# bristol_longshot.net
KiCad netlist of a schematic drawn in EAGLE
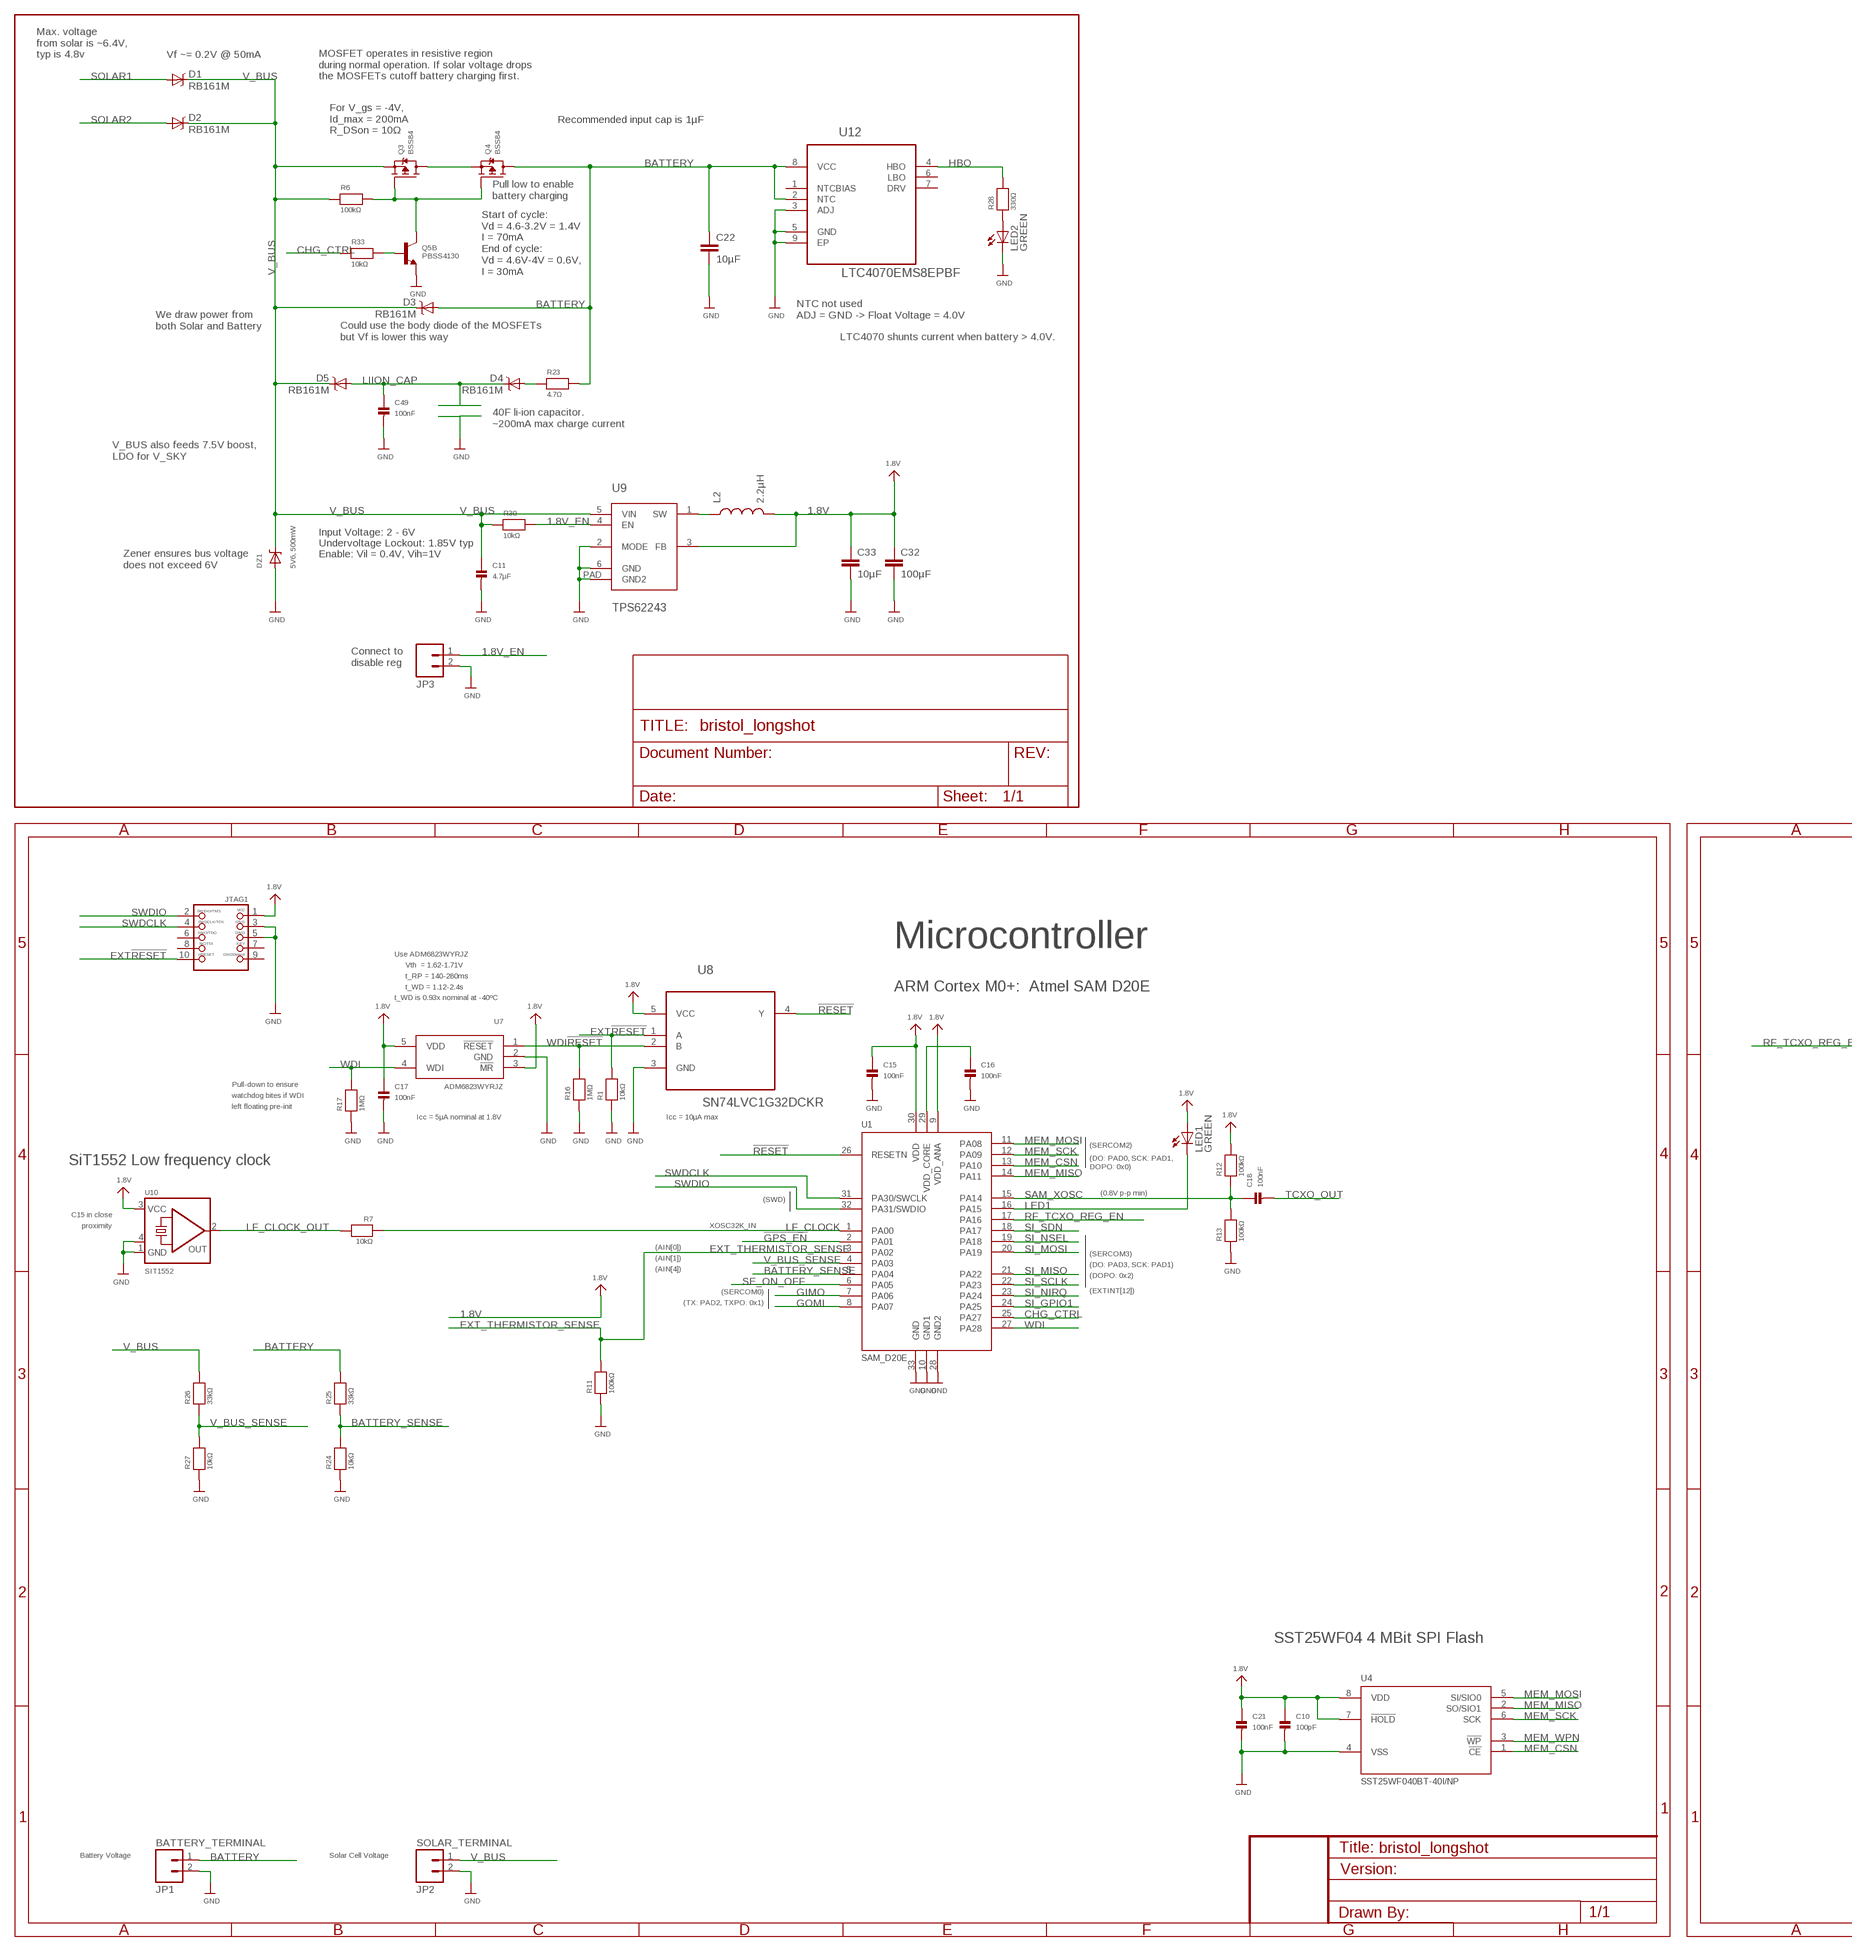
[diagram p0: schematic, sheet 1, part 1 of 3]
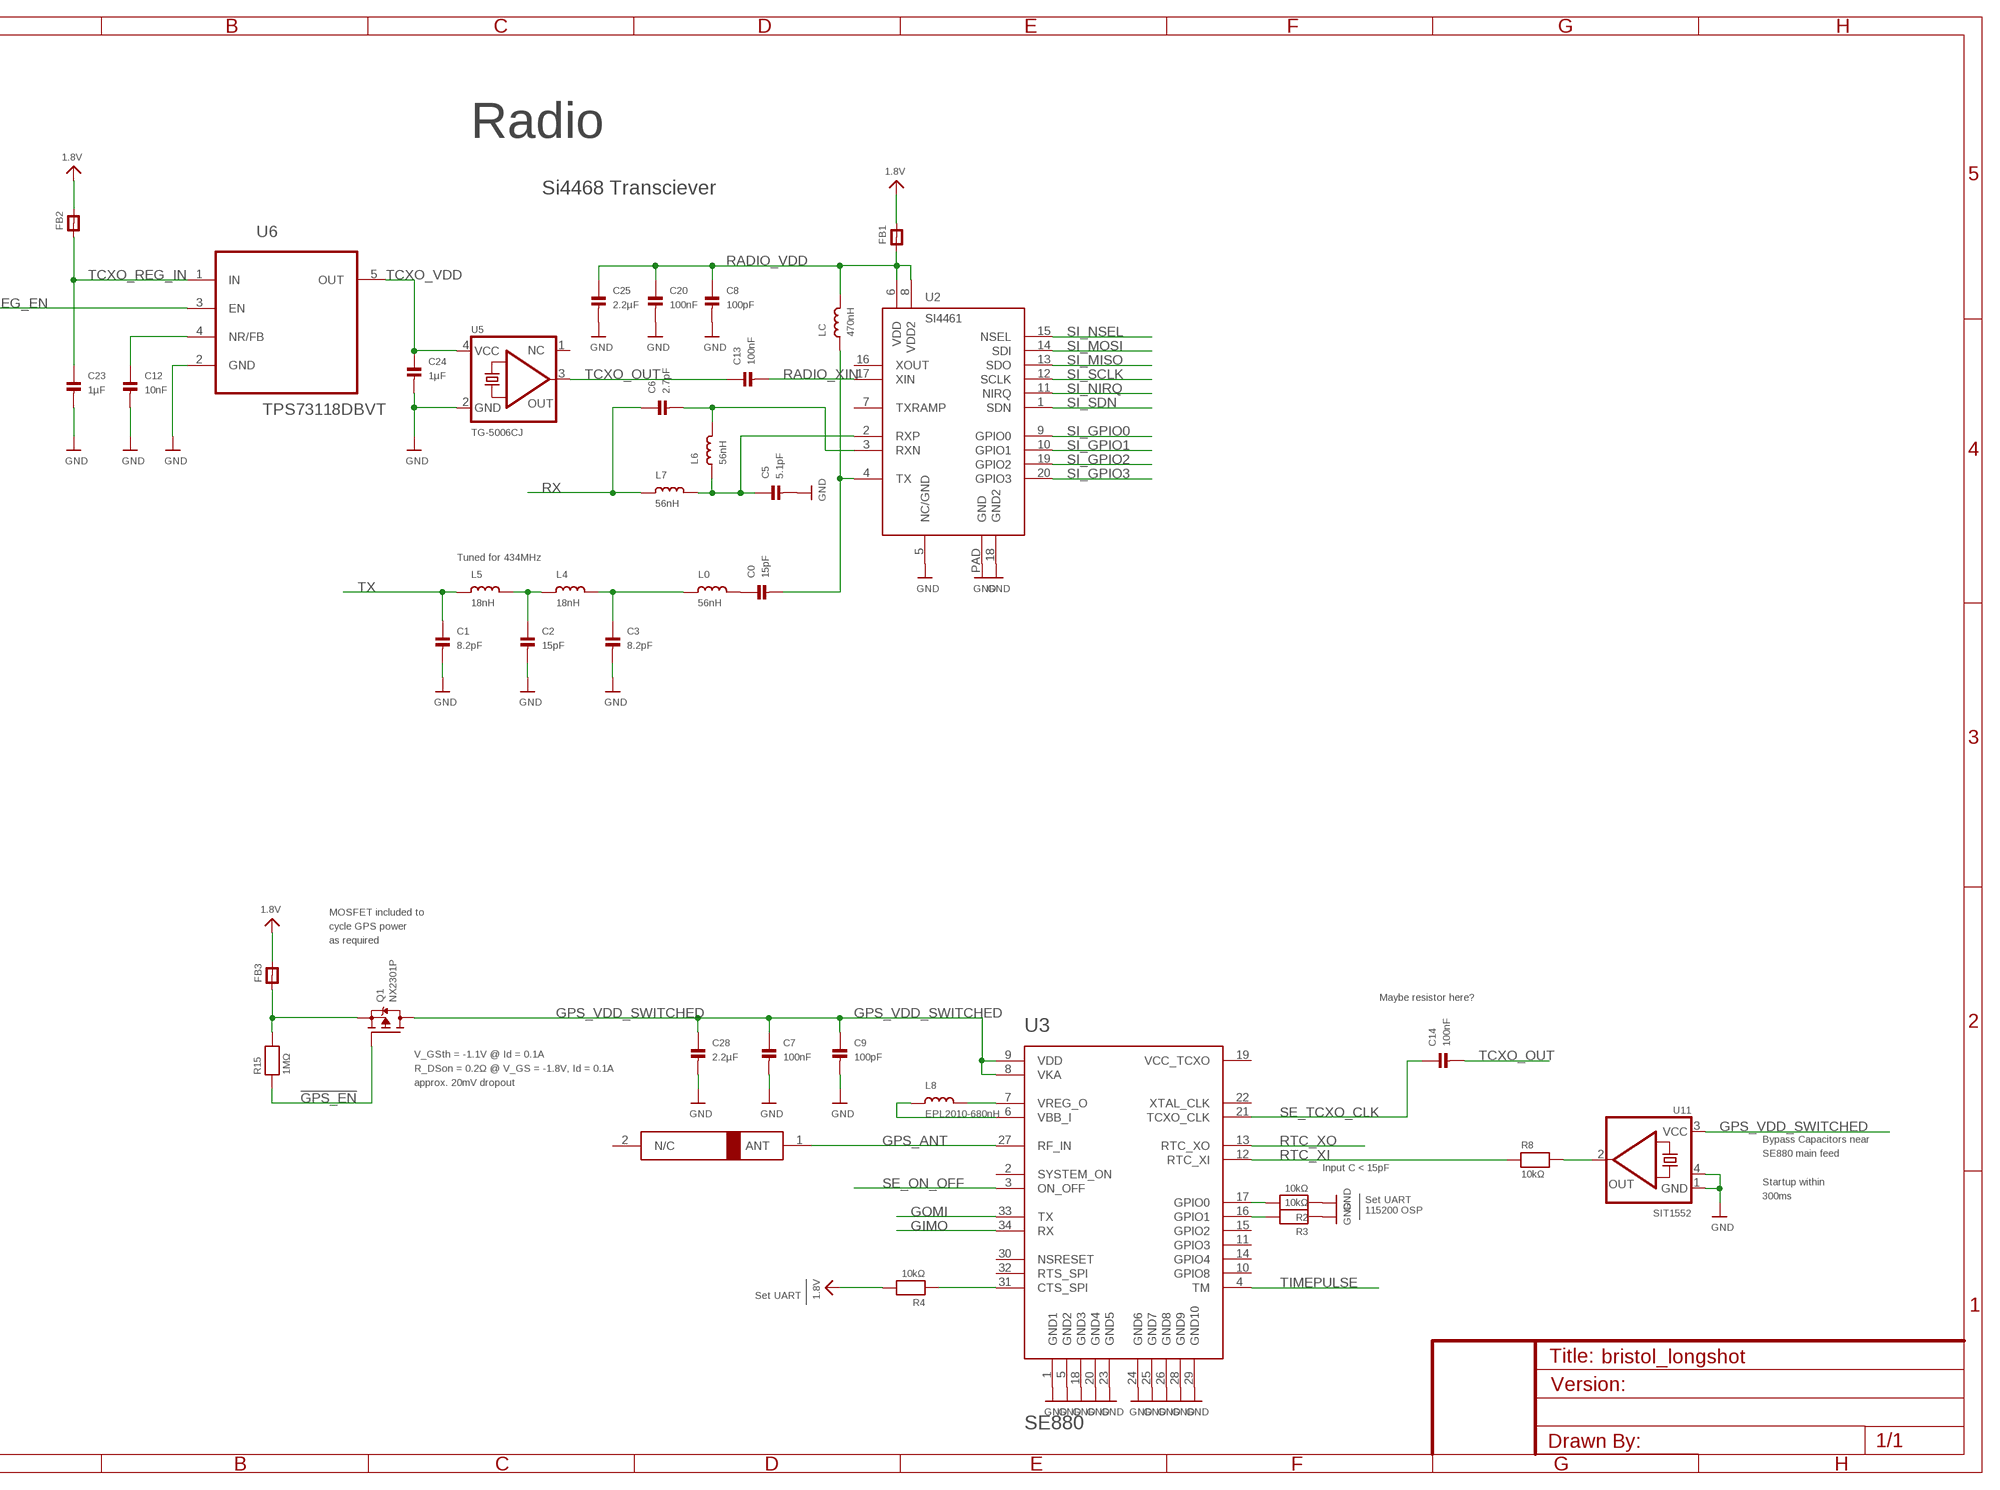
[diagram p1: schematic, sheet 1, part 2 of 3]
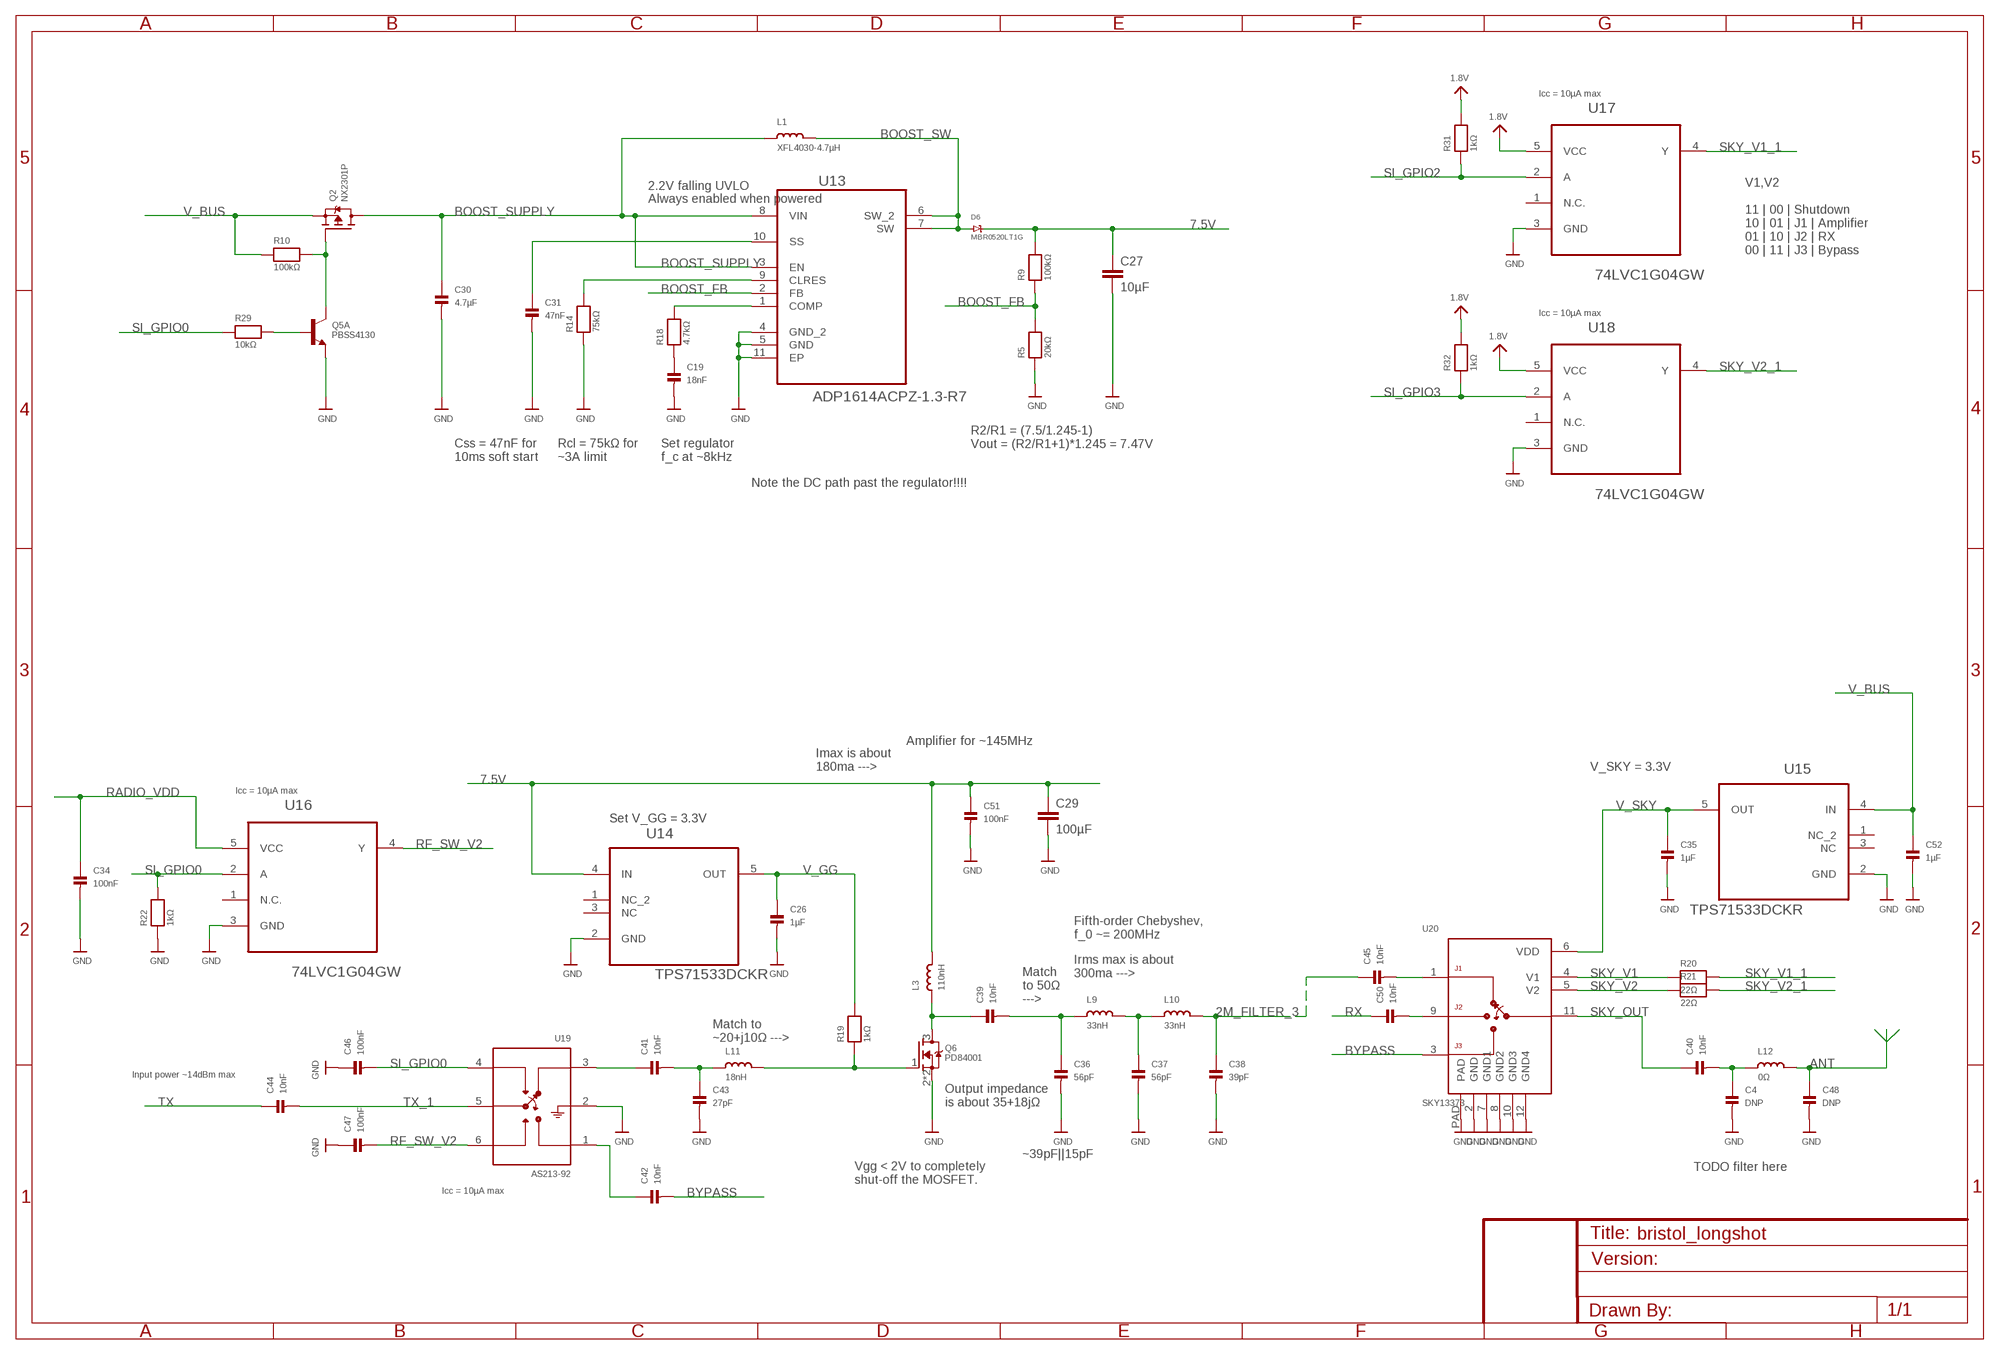
[diagram p2: schematic, sheet 1, part 3 of 3]

(export (version "E")
  (design (tool "Eeschema 10.0.6"))
  (components
    (comp (ref "A1")
      (value "1575AT43A40")
      (footprint "eagle-import:1575AT43A40")
      (libsource (lib "eagle-import") (part "1575AT43A40"))
    )
    (comp (ref "C0")
      (value "15pF")
      (footprint "eagle-import:_0402")
      (libsource (lib "eagle-import") (part "CAP_CERAMIC_0402"))
    )
    (comp (ref "C1")
      (value "8.2pF")
      (footprint "eagle-import:_0402")
      (libsource (lib "eagle-import") (part "CAP_CERAMIC_0402"))
    )
    (comp (ref "C2")
      (value "15pF")
      (footprint "eagle-import:_0402")
      (libsource (lib "eagle-import") (part "CAP_CERAMIC_0402"))
    )
    (comp (ref "C3")
      (value "8.2pF")
      (footprint "eagle-import:_0402")
      (libsource (lib "eagle-import") (part "CAP_CERAMIC_0402"))
    )
    (comp (ref "C4")
      (value "DNP")
      (footprint "eagle-import:_0402")
      (libsource (lib "eagle-import") (part "CAP_CERAMIC_0402"))
    )
    (comp (ref "C5")
      (value "5.1pF")
      (footprint "eagle-import:_0402")
      (libsource (lib "eagle-import") (part "CAP_CERAMIC_0402"))
    )
    (comp (ref "C6")
      (value "2.7pF")
      (footprint "eagle-import:_0402")
      (libsource (lib "eagle-import") (part "CAP_CERAMIC_0402"))
    )
    (comp (ref "C7")
      (value "100nF")
      (footprint "eagle-import:_0402")
      (libsource (lib "eagle-import") (part "CAP_CERAMIC_0402"))
    )
    (comp (ref "C8")
      (value "100pF")
      (footprint "eagle-import:_0402")
      (libsource (lib "eagle-import") (part "CAP_CERAMIC_0402"))
    )
    (comp (ref "C9")
      (value "100pF")
      (footprint "eagle-import:_0402")
      (libsource (lib "eagle-import") (part "CAP_CERAMIC_0402"))
    )
    (comp (ref "C10")
      (value "100pF")
      (footprint "eagle-import:_0402")
      (libsource (lib "eagle-import") (part "CAP_CERAMIC_0402"))
    )
    (comp (ref "C11")
      (value "4.7µF")
      (footprint "eagle-import:_0402")
      (libsource (lib "eagle-import") (part "CAP_CERAMIC_0402"))
    )
    (comp (ref "C12")
      (value "10nF")
      (footprint "eagle-import:_0402")
      (libsource (lib "eagle-import") (part "CAP_CERAMIC_0402"))
    )
    (comp (ref "C13")
      (value "100nF")
      (footprint "eagle-import:_0402")
      (libsource (lib "eagle-import") (part "CAP_CERAMIC_0402"))
    )
    (comp (ref "C14")
      (value "100nF")
      (footprint "eagle-import:_0402")
      (libsource (lib "eagle-import") (part "CAP_CERAMIC_0402"))
    )
    (comp (ref "C15")
      (value "100nF")
      (footprint "eagle-import:_0402")
      (libsource (lib "eagle-import") (part "CAP_CERAMIC_0402"))
    )
    (comp (ref "C16")
      (value "100nF")
      (footprint "eagle-import:_0402")
      (libsource (lib "eagle-import") (part "CAP_CERAMIC_0402"))
    )
    (comp (ref "C17")
      (value "100nF")
      (footprint "eagle-import:_0402")
      (libsource (lib "eagle-import") (part "CAP_CERAMIC_0402"))
    )
    (comp (ref "C18")
      (value "100nF")
      (footprint "eagle-import:_0402")
      (libsource (lib "eagle-import") (part "CAP_CERAMIC_0402"))
    )
    (comp (ref "C19")
      (value "18nF")
      (footprint "eagle-import:_0402")
      (libsource (lib "eagle-import") (part "CAP_CERAMIC_0402"))
    )
    (comp (ref "C20")
      (value "100nF")
      (footprint "eagle-import:_0402")
      (libsource (lib "eagle-import") (part "CAP_CERAMIC_0402"))
    )
    (comp (ref "C21")
      (value "100nF")
      (footprint "eagle-import:_0402")
      (libsource (lib "eagle-import") (part "CAP_CERAMIC_0402"))
    )
    (comp (ref "C22")
      (value "10µF")
      (footprint "eagle-import:C0603K")
      (libsource (lib "eagle-import") (part "C-EUC0603K"))
    )
    (comp (ref "C23")
      (value "1µF")
      (footprint "eagle-import:_0402")
      (libsource (lib "eagle-import") (part "CAP_CERAMIC_0402"))
    )
    (comp (ref "C24")
      (value "1µF")
      (footprint "eagle-import:_0402")
      (libsource (lib "eagle-import") (part "CAP_CERAMIC_0402"))
    )
    (comp (ref "C25")
      (value "2.2µF")
      (footprint "eagle-import:_0402")
      (libsource (lib "eagle-import") (part "CAP_CERAMIC_0402"))
    )
    (comp (ref "C26")
      (value "1µF")
      (footprint "eagle-import:_0402")
      (libsource (lib "eagle-import") (part "CAP_CERAMIC_0402"))
    )
    (comp (ref "C27")
      (value "10µF")
      (footprint "eagle-import:C0603K")
      (libsource (lib "eagle-import") (part "C-EUC0603K"))
    )
    (comp (ref "C28")
      (value "2.2µF")
      (footprint "eagle-import:_0402")
      (libsource (lib "eagle-import") (part "CAP_CERAMIC_0402"))
    )
    (comp (ref "C29")
      (value "100µF")
      (footprint "eagle-import:C1206K")
      (libsource (lib "eagle-import") (part "C-EUC1206K"))
    )
    (comp (ref "C30")
      (value "4.7µF")
      (footprint "eagle-import:_0402")
      (libsource (lib "eagle-import") (part "CAP_CERAMIC_0402"))
    )
    (comp (ref "C31")
      (value "47nF")
      (footprint "eagle-import:_0402")
      (libsource (lib "eagle-import") (part "CAP_CERAMIC_0402"))
    )
    (comp (ref "C32")
      (value "100µF")
      (footprint "eagle-import:C1206K")
      (libsource (lib "eagle-import") (part "C-EUC1206K"))
    )
    (comp (ref "C33")
      (value "10µF")
      (footprint "eagle-import:C0603K")
      (libsource (lib "eagle-import") (part "C-EUC0603K"))
    )
    (comp (ref "C34")
      (value "100nF")
      (footprint "eagle-import:_0402")
      (libsource (lib "eagle-import") (part "CAP_CERAMIC_0402"))
    )
    (comp (ref "C35")
      (value "1µF")
      (footprint "eagle-import:_0402")
      (libsource (lib "eagle-import") (part "CAP_CERAMIC_0402"))
    )
    (comp (ref "C36")
      (value "56pF")
      (footprint "eagle-import:_0402")
      (libsource (lib "eagle-import") (part "CAP_CERAMIC_0402"))
    )
    (comp (ref "C37")
      (value "56pF")
      (footprint "eagle-import:_0402")
      (libsource (lib "eagle-import") (part "CAP_CERAMIC_0402"))
    )
    (comp (ref "C38")
      (value "39pF")
      (footprint "eagle-import:_0402")
      (libsource (lib "eagle-import") (part "CAP_CERAMIC_0402"))
    )
    (comp (ref "C39")
      (value "10nF")
      (footprint "eagle-import:_0402")
      (libsource (lib "eagle-import") (part "CAP_CERAMIC_0402"))
    )
    (comp (ref "C40")
      (value "10nF")
      (footprint "eagle-import:_0402")
      (libsource (lib "eagle-import") (part "CAP_CERAMIC_0402"))
    )
    (comp (ref "C41")
      (value "10nF")
      (footprint "eagle-import:_0402")
      (libsource (lib "eagle-import") (part "CAP_CERAMIC_0402"))
    )
    (comp (ref "C42")
      (value "10nF")
      (footprint "eagle-import:_0402")
      (libsource (lib "eagle-import") (part "CAP_CERAMIC_0402"))
    )
    (comp (ref "C43")
      (value "27pF")
      (footprint "eagle-import:_0402")
      (libsource (lib "eagle-import") (part "CAP_CERAMIC_0402"))
    )
    (comp (ref "C44")
      (value "10nF")
      (footprint "eagle-import:_0402")
      (libsource (lib "eagle-import") (part "CAP_CERAMIC_0402"))
    )
    (comp (ref "C45")
      (value "10nF")
      (footprint "eagle-import:_0402")
      (libsource (lib "eagle-import") (part "CAP_CERAMIC_0402"))
    )
    (comp (ref "C46")
      (value "100nF")
      (footprint "eagle-import:_0402")
      (libsource (lib "eagle-import") (part "CAP_CERAMIC_0402"))
    )
    (comp (ref "C47")
      (value "100nF")
      (footprint "eagle-import:_0402")
      (libsource (lib "eagle-import") (part "CAP_CERAMIC_0402"))
    )
    (comp (ref "C48")
      (value "DNP")
      (footprint "eagle-import:_0402")
      (libsource (lib "eagle-import") (part "CAP_CERAMIC_0402"))
    )
    (comp (ref "C49")
      (value "100nF")
      (footprint "eagle-import:_0402")
      (libsource (lib "eagle-import") (part "CAP_CERAMIC_0402"))
    )
    (comp (ref "C50")
      (value "10nF")
      (footprint "eagle-import:_0805")
      (libsource (lib "eagle-import") (part "CAP_CERAMIC_0805"))
    )
    (comp (ref "C51")
      (value "100nF")
      (footprint "eagle-import:_0402")
      (libsource (lib "eagle-import") (part "CAP_CERAMIC_0402"))
    )
    (comp (ref "C52")
      (value "1µF")
      (footprint "eagle-import:_0402")
      (libsource (lib "eagle-import") (part "CAP_CERAMIC_0402"))
    )
    (comp (ref "D1")
      (value "RB161M")
      (footprint "eagle-import:RB161M")
      (libsource (lib "eagle-import") (part "RB161M"))
    )
    (comp (ref "D2")
      (value "RB161M")
      (footprint "eagle-import:RB161M")
      (libsource (lib "eagle-import") (part "RB161M"))
    )
    (comp (ref "D3")
      (value "RB161M")
      (footprint "eagle-import:RB161M")
      (libsource (lib "eagle-import") (part "RB161M"))
    )
    (comp (ref "D4")
      (value "RB161M")
      (footprint "eagle-import:RB161M")
      (libsource (lib "eagle-import") (part "RB161M"))
    )
    (comp (ref "D5")
      (value "RB161M")
      (footprint "eagle-import:RB161M")
      (libsource (lib "eagle-import") (part "RB161M"))
    )
    (comp (ref "D6")
      (value "MBR0520LT1G")
      (footprint "eagle-import:SOD123W")
      (libsource (lib "eagle-import") (part "DIODE[SCHOTKY]-SOD123W"))
    )
    (comp (ref "DZ1")
      (value "5V6, 500mW")
      (footprint "eagle-import:SOD-323")
      (libsource (lib "eagle-import") (part "DIODE-ZENERSOD"))
    )
    (comp (ref "FB1")
      (value "FERRITE_0402")
      (footprint "eagle-import:_0402")
      (libsource (lib "eagle-import") (part "FERRITE_0402"))
    )
    (comp (ref "FB2")
      (value "FERRITE_0402")
      (footprint "eagle-import:_0402")
      (libsource (lib "eagle-import") (part "FERRITE_0402"))
    )
    (comp (ref "FB3")
      (value "FERRITE_0603")
      (footprint "eagle-import:_0603")
      (libsource (lib "eagle-import") (part "FERRITE_0603"))
    )
    (comp (ref "JP1")
      (value "BATTERY_TERMINAL")
      (footprint "eagle-import:1X02_LOCK")
      (libsource (lib "eagle-import") (part "M02LOCK"))
    )
    (comp (ref "JP2")
      (value "SOLAR_TERMINAL")
      (footprint "eagle-import:1X02_LOCK")
      (libsource (lib "eagle-import") (part "M02LOCK"))
    )
    (comp (ref "JP3")
      (value "M02LOCK")
      (footprint "eagle-import:1X02_LOCK")
      (libsource (lib "eagle-import") (part "M02LOCK"))
    )
    (comp (ref "JTAG1")
      (value "JTAG-CORTEXM3SMT")
      (footprint "eagle-import:2X05_1.27MM_SMT")
      (libsource (lib "eagle-import") (part "JTAG-CORTEXM3SMT"))
    )
    (comp (ref "L0")
      (value "56nH")
      (footprint "eagle-import:_0402@2")
      (libsource (lib "eagle-import") (part "INDUCTOR_0402"))
    )
    (comp (ref "L1")
      (value "XFL4030-4.7µH")
      (footprint "eagle-import:XFL4020")
      (libsource (lib "eagle-import") (part "XFL4020"))
    )
    (comp (ref "L2")
      (value "2.2µH")
      (footprint "eagle-import:1007")
      (libsource (lib "eagle-import") (part "INDUCTOR1007"))
    )
    (comp (ref "L3")
      (value "110nH")
      (footprint "eagle-import:_0805MP")
      (libsource (lib "eagle-import") (part "INDUCTOR_0805MP"))
    )
    (comp (ref "L4")
      (value "18nH")
      (footprint "eagle-import:_0402@2")
      (libsource (lib "eagle-import") (part "INDUCTOR_0402"))
    )
    (comp (ref "L5")
      (value "18nH")
      (footprint "eagle-import:_0402@2")
      (libsource (lib "eagle-import") (part "INDUCTOR_0402"))
    )
    (comp (ref "L6")
      (value "56nH")
      (footprint "eagle-import:_0402@2")
      (libsource (lib "eagle-import") (part "INDUCTOR_0402"))
    )
    (comp (ref "L7")
      (value "56nH")
      (footprint "eagle-import:_0402@2")
      (libsource (lib "eagle-import") (part "INDUCTOR_0402"))
    )
    (comp (ref "L8")
      (value "EPL2010-680nH")
      (footprint "eagle-import:EPL2010")
      (libsource (lib "eagle-import") (part "EPL2010"))
    )
    (comp (ref "L9")
      (value "33nH")
      (footprint "eagle-import:_0603MP")
      (libsource (lib "eagle-import") (part "INDUCTOR_0603MP"))
    )
    (comp (ref "L10")
      (value "33nH")
      (footprint "eagle-import:_0603MP")
      (libsource (lib "eagle-import") (part "INDUCTOR_0603MP"))
    )
    (comp (ref "L11")
      (value "18nH")
      (footprint "eagle-import:_0402@2")
      (libsource (lib "eagle-import") (part "INDUCTOR_0402"))
    )
    (comp (ref "L12")
      (value "0Ω")
      (footprint "eagle-import:_0402@2")
      (libsource (lib "eagle-import") (part "INDUCTOR_0402"))
    )
    (comp (ref "LC")
      (value "470nH")
      (footprint "eagle-import:_0402@2")
      (libsource (lib "eagle-import") (part "INDUCTOR_0402"))
    )
    (comp (ref "LED1")
      (value "GREEN")
      (footprint "eagle-import:CHIPLED_0603")
      (libsource (lib "eagle-import") (part "LEDCHIPLED_0603"))
    )
    (comp (ref "LED2")
      (value "GREEN")
      (footprint "eagle-import:CHIPLED_0603")
      (libsource (lib "eagle-import") (part "LEDCHIPLED_0603"))
    )
    (comp (ref "Q1")
      (value "NX2301P")
      (footprint "eagle-import:SOT23")
      (libsource (lib "eagle-import") (part "NX2301P"))
    )
    (comp (ref "Q2")
      (value "NX2301P")
      (footprint "eagle-import:SOT23")
      (libsource (lib "eagle-import") (part "NX2301P"))
    )
    (comp (ref "Q3")
      (value "BSS84")
      (footprint "eagle-import:SOT23")
      (libsource (lib "eagle-import") (part "NX2301P"))
    )
    (comp (ref "Q4")
      (value "BSS84")
      (footprint "eagle-import:SOT23")
      (libsource (lib "eagle-import") (part "NX2301P"))
    )
    (comp (ref "Q5")
      (value "PBSS4130")
      (footprint "eagle-import:SOT1118")
      (libsource (lib "eagle-import") (part "PBSS4130"))
    )
    (comp (ref "Q6")
      (value "PD84001")
      (footprint "eagle-import:SOT-89")
      (libsource (lib "eagle-import") (part "PD84001"))
    )
    (comp (ref "R1")
      (value "10kΩ")
      (footprint "eagle-import:_0402")
      (libsource (lib "eagle-import") (part "RESISTOR_0402"))
    )
    (comp (ref "R2")
      (value "10kΩ")
      (footprint "eagle-import:_0402")
      (libsource (lib "eagle-import") (part "RESISTOR_0402"))
    )
    (comp (ref "R3")
      (value "10kΩ")
      (footprint "eagle-import:_0402")
      (libsource (lib "eagle-import") (part "RESISTOR_0402"))
    )
    (comp (ref "R4")
      (value "10kΩ")
      (footprint "eagle-import:_0402")
      (libsource (lib "eagle-import") (part "RESISTOR_0402"))
    )
    (comp (ref "R5")
      (value "20kΩ")
      (footprint "eagle-import:_0402")
      (libsource (lib "eagle-import") (part "RESISTOR_0402"))
    )
    (comp (ref "R6")
      (value "100kΩ")
      (footprint "eagle-import:_0402")
      (libsource (lib "eagle-import") (part "RESISTOR_0402"))
    )
    (comp (ref "R7")
      (value "10kΩ")
      (footprint "eagle-import:_0402")
      (libsource (lib "eagle-import") (part "RESISTOR_0402"))
    )
    (comp (ref "R8")
      (value "10kΩ")
      (footprint "eagle-import:_0402")
      (libsource (lib "eagle-import") (part "RESISTOR_0402"))
    )
    (comp (ref "R9")
      (value "100kΩ")
      (footprint "eagle-import:_0402")
      (libsource (lib "eagle-import") (part "RESISTOR_0402"))
    )
    (comp (ref "R10")
      (value "100kΩ")
      (footprint "eagle-import:_0402")
      (libsource (lib "eagle-import") (part "RESISTOR_0402"))
    )
    (comp (ref "R11")
      (value "100kΩ")
      (footprint "eagle-import:_0402")
      (libsource (lib "eagle-import") (part "RESISTOR_0402"))
    )
    (comp (ref "R12")
      (value "100kΩ")
      (footprint "eagle-import:_0402")
      (libsource (lib "eagle-import") (part "RESISTOR_0402"))
    )
    (comp (ref "R13")
      (value "100kΩ")
      (footprint "eagle-import:_0402")
      (libsource (lib "eagle-import") (part "RESISTOR_0402"))
    )
    (comp (ref "R14")
      (value "75kΩ")
      (footprint "eagle-import:_0402")
      (libsource (lib "eagle-import") (part "RESISTOR_0402"))
    )
    (comp (ref "R15")
      (value "1MΩ")
      (footprint "eagle-import:_0402")
      (libsource (lib "eagle-import") (part "RESISTOR_0402"))
    )
    (comp (ref "R16")
      (value "1MΩ")
      (footprint "eagle-import:_0402")
      (libsource (lib "eagle-import") (part "RESISTOR_0402"))
    )
    (comp (ref "R17")
      (value "1MΩ")
      (footprint "eagle-import:_0402")
      (libsource (lib "eagle-import") (part "RESISTOR_0402"))
    )
    (comp (ref "R18")
      (value "4.7kΩ")
      (footprint "eagle-import:_0402")
      (libsource (lib "eagle-import") (part "RESISTOR_0402"))
    )
    (comp (ref "R19")
      (value "1kΩ")
      (footprint "eagle-import:_0402")
      (libsource (lib "eagle-import") (part "RESISTOR_0402"))
    )
    (comp (ref "R20")
      (value "22Ω")
      (footprint "eagle-import:_0603MP")
      (libsource (lib "eagle-import") (part "RESISTOR_0603MP"))
    )
    (comp (ref "R21")
      (value "22Ω")
      (footprint "eagle-import:_0603MP")
      (libsource (lib "eagle-import") (part "RESISTOR_0603MP"))
    )
    (comp (ref "R22")
      (value "1kΩ")
      (footprint "eagle-import:_0402")
      (libsource (lib "eagle-import") (part "RESISTOR_0402"))
    )
    (comp (ref "R23")
      (value "4.7Ω")
      (footprint "eagle-import:_0402")
      (libsource (lib "eagle-import") (part "RESISTOR_0402"))
    )
    (comp (ref "R24")
      (value "10kΩ")
      (footprint "eagle-import:_0402")
      (libsource (lib "eagle-import") (part "RESISTOR_0402"))
    )
    (comp (ref "R25")
      (value "33kΩ")
      (footprint "eagle-import:_0402")
      (libsource (lib "eagle-import") (part "RESISTOR_0402"))
    )
    (comp (ref "R26")
      (value "33kΩ")
      (footprint "eagle-import:_0402")
      (libsource (lib "eagle-import") (part "RESISTOR_0402"))
    )
    (comp (ref "R27")
      (value "10kΩ")
      (footprint "eagle-import:_0402")
      (libsource (lib "eagle-import") (part "RESISTOR_0402"))
    )
    (comp (ref "R28")
      (value "330Ω")
      (footprint "eagle-import:_0402")
      (libsource (lib "eagle-import") (part "RESISTOR_0402"))
    )
    (comp (ref "R29")
      (value "10kΩ")
      (footprint "eagle-import:_0402")
      (libsource (lib "eagle-import") (part "RESISTOR_0402"))
    )
    (comp (ref "R30")
      (value "10kΩ")
      (footprint "eagle-import:_0402")
      (libsource (lib "eagle-import") (part "RESISTOR_0402"))
    )
    (comp (ref "R31")
      (value "1kΩ")
      (footprint "eagle-import:_0402")
      (libsource (lib "eagle-import") (part "RESISTOR_0402"))
    )
    (comp (ref "R32")
      (value "1kΩ")
      (footprint "eagle-import:_0402")
      (libsource (lib "eagle-import") (part "RESISTOR_0402"))
    )
    (comp (ref "R33")
      (value "10kΩ")
      (footprint "eagle-import:_0402")
      (libsource (lib "eagle-import") (part "RESISTOR_0402"))
    )
    (comp (ref "U1")
      (value "SAM_D20E")
      (footprint "eagle-import:QFN32_5MM")
      (libsource (lib "eagle-import") (part "SAM_D20E"))
    )
    (comp (ref "U2")
      (value "SI4461")
      (footprint "eagle-import:QFN20")
      (libsource (lib "eagle-import") (part "SI4060"))
    )
    (comp (ref "U3")
      (value "SE880")
      (footprint "eagle-import:SE880")
      (libsource (lib "eagle-import") (part "SE880"))
    )
    (comp (ref "U4")
      (value "SST25WF040BT-40I/NP")
      (footprint "eagle-import:USON-8")
      (libsource (lib "eagle-import") (part "SST25WF040BT-40I/NP"))
    )
    (comp (ref "U5")
      (value "TG-5006CJ")
      (footprint "eagle-import:TC-5006CJ")
      (libsource (lib "eagle-import") (part "TG-5006CJ"))
    )
    (comp (ref "U6")
      (value "TPS73118DBVT")
      (footprint "eagle-import:SOT95P280X145-5N")
      (libsource (lib "eagle-import") (part "TPS73118DBVT"))
    )
    (comp (ref "U7")
      (value "ADM6823WYRJZ")
      (footprint "eagle-import:SOT23-5")
      (libsource (lib "eagle-import") (part "TPS3123"))
    )
    (comp (ref "U8")
      (value "SN74LVC1G32DCKR")
      (footprint "eagle-import:SOT65P210X110-5N")
      (libsource (lib "eagle-import") (part "SN74LVC1G32DCKR"))
    )
    (comp (ref "U9")
      (value "TPS62243")
      (footprint "eagle-import:S-PWSON-N6")
      (libsource (lib "eagle-import") (part "TPS62243"))
    )
    (comp (ref "U10")
      (value "SIT1552")
      (footprint "eagle-import:SIT1552")
      (libsource (lib "eagle-import") (part "SIT1552"))
    )
    (comp (ref "U11")
      (value "SIT1552")
      (footprint "eagle-import:SIT1552")
      (libsource (lib "eagle-import") (part "SIT1552"))
    )
    (comp (ref "U12")
      (value "LTC4070EMS8EPBF")
      (footprint "eagle-import:SOP65P490X110-9N")
      (fields (field (name "MPN") "LTC4070EMS8E#PBF"))
      (libsource (lib "eagle-import") (part "LTC4070EMS8EPBF"))
    )
    (comp (ref "U13")
      (value "ADP1614ACPZ-1.3-R7")
      (footprint "eagle-import:DFN50P300X300X80-11N")
      (libsource (lib "eagle-import") (part "ADP1614ACPZ-1.3-R7"))
    )
    (comp (ref "U14")
      (value "TPS71533DCKR")
      (footprint "eagle-import:SOT65P210X110-5N")
      (libsource (lib "eagle-import") (part "TPS71533DCKR"))
    )
    (comp (ref "U15")
      (value "TPS71533DCKR")
      (footprint "eagle-import:SOT65P210X110-5N")
      (libsource (lib "eagle-import") (part "TPS71533DCKR"))
    )
    (comp (ref "U16")
      (value "74LVC1G04GW")
      (footprint "eagle-import:SOT65P210X110-5N")
      (libsource (lib "eagle-import") (part "74LVC1G04GW"))
    )
    (comp (ref "U17")
      (value "74LVC1G04GW")
      (footprint "eagle-import:SOT65P210X110-5N")
      (libsource (lib "eagle-import") (part "74LVC1G04GW"))
    )
    (comp (ref "U18")
      (value "74LVC1G04GW")
      (footprint "eagle-import:SOT65P210X110-5N")
      (libsource (lib "eagle-import") (part "74LVC1G04GW"))
    )
    (comp (ref "U19")
      (value "AS213-92")
      (footprint "eagle-import:SOT-6")
      (libsource (lib "eagle-import") (part "AS213-92"))
    )
    (comp (ref "U20")
      (value "SKY13373")
      (footprint "eagle-import:SKY13373")
      (libsource (lib "eagle-import") (part "SKY13373"))
    )
  )
  (nets
    (net (code "1") (name "/1.8V_EN") (class "Default")
      (node (ref "JP3") (pin "1") (pinfunction "1_1") (pintype "passive"))
      (node (ref "R30") (pin "2") (pinfunction "2_2") (pintype "passive"))
      (node (ref "U9") (pin "4") (pinfunction "EN_4") (pintype "bidirectional"))
    )
    (net (code "2") (name "/2M_FILTER_3") (class "Default")
      (node (ref "C38") (pin "1") (pinfunction "P$1_1") (pintype "passive"))
      (node (ref "C45") (pin "1") (pinfunction "P$1_1") (pintype "passive"))
      (node (ref "L10") (pin "2") (pinfunction "2_2") (pintype "passive"))
    )
    (net (code "3") (name "/7.5V") (class "Default")
      (node (ref "C27") (pin "1") (pinfunction "1_1") (pintype "passive"))
      (node (ref "C29") (pin "1") (pinfunction "1_1") (pintype "passive"))
      (node (ref "C51") (pin "1") (pinfunction "P$1_1") (pintype "passive"))
      (node (ref "D6") (pin "P$2") (pinfunction "2_P$2") (pintype "bidirectional"))
      (node (ref "L3") (pin "2") (pinfunction "2_2") (pintype "passive"))
      (node (ref "R9") (pin "2") (pinfunction "2_2") (pintype "passive"))
      (node (ref "U14") (pin "4") (pinfunction "IN_4") (pintype "power_in"))
    )
    (net (code "4") (name "/ANT") (class "Default")
      (node (ref "C48") (pin "1") (pinfunction "P$1_1") (pintype "passive"))
      (node (ref "L12") (pin "2") (pinfunction "2_2") (pintype "passive"))
    )
    (net (code "5") (name "/BATTERY") (class "Default")
      (node (ref "C22") (pin "1") (pinfunction "1_1") (pintype "passive"))
      (node (ref "D3") (pin "ANODE") (pinfunction "A_ANODE") (pintype "passive"))
      (node (ref "JP1") (pin "1") (pinfunction "1_1") (pintype "passive"))
      (node (ref "Q4") (pin "3") (pinfunction "D_3") (pintype "passive"))
      (node (ref "R23") (pin "2") (pinfunction "2_2") (pintype "passive"))
      (node (ref "R25") (pin "2") (pinfunction "2_2") (pintype "passive"))
      (node (ref "U12") (pin "2") (pinfunction "NTC_2") (pintype "input"))
      (node (ref "U12") (pin "8") (pinfunction "VCC_8") (pintype "power_in"))
    )
    (net (code "6") (name "/BATTERY_SENSE") (class "Default")
      (node (ref "R24") (pin "2") (pinfunction "2_2") (pintype "passive"))
      (node (ref "R25") (pin "1") (pinfunction "1_1") (pintype "passive"))
      (node (ref "U1") (pin "5") (pinfunction "PA04_5") (pintype "bidirectional"))
    )
    (net (code "7") (name "/BOOST_FB") (class "Default")
      (node (ref "R5") (pin "2") (pinfunction "2_2") (pintype "passive"))
      (node (ref "R9") (pin "1") (pinfunction "1_1") (pintype "passive"))
      (node (ref "U13") (pin "2") (pinfunction "FB_2") (pintype "input"))
    )
    (net (code "8") (name "/BOOST_SUPPLY") (class "Default")
      (node (ref "C30") (pin "1") (pinfunction "P$1_1") (pintype "passive"))
      (node (ref "L1") (pin "1") (pinfunction "1_1") (pintype "passive"))
      (node (ref "Q2") (pin "3") (pinfunction "D_3") (pintype "passive"))
      (node (ref "U13") (pin "3") (pinfunction "EN_3") (pintype "input"))
      (node (ref "U13") (pin "8") (pinfunction "VIN_8") (pintype "power_in"))
    )
    (net (code "9") (name "/BOOST_SW") (class "Default")
      (node (ref "D6") (pin "P$1") (pinfunction "1_P$1") (pintype "bidirectional"))
      (node (ref "L1") (pin "2") (pinfunction "2_2") (pintype "passive"))
      (node (ref "U13") (pin "6") (pinfunction "SW_2_6") (pintype "output"))
      (node (ref "U13") (pin "7") (pinfunction "SW_7") (pintype "output"))
    )
    (net (code "10") (name "/BYPASS") (class "Default")
      (node (ref "C42") (pin "2") (pinfunction "P$2_2") (pintype "passive"))
      (node (ref "U20") (pin "3") (pinfunction "J3_3") (pintype "bidirectional"))
    )
    (net (code "11") (name "/CHG_CTRL") (class "Default")
      (node (ref "R33") (pin "1") (pinfunction "1_1") (pintype "passive"))
      (node (ref "U1") (pin "25") (pinfunction "PA27_25") (pintype "bidirectional"))
    )
    (net (code "12") (name "/EXT_THERMISTOR_SENSE") (class "Default")
      (node (ref "R11") (pin "2") (pinfunction "2_2") (pintype "passive"))
      (node (ref "U1") (pin "3") (pinfunction "PA02_3") (pintype "bidirectional"))
    )
    (net (code "13") (name "/EXT~{RESET}") (class "Default")
      (node (ref "JTAG1") (pin "10") (pinfunction "10_10") (pintype "passive"))
      (node (ref "R1") (pin "2") (pinfunction "2_2") (pintype "passive"))
      (node (ref "U8") (pin "1") (pinfunction "A_1") (pintype "input"))
    )
    (net (code "14") (name "/GIMO") (class "Default")
      (node (ref "U1") (pin "7") (pinfunction "PA06_7") (pintype "bidirectional"))
      (node (ref "U3") (pin "34") (pinfunction "RX_34") (pintype "bidirectional"))
    )
    (net (code "15") (name "/GOMI") (class "Default")
      (node (ref "U1") (pin "8") (pinfunction "PA07_8") (pintype "bidirectional"))
      (node (ref "U3") (pin "33") (pinfunction "TX_33") (pintype "bidirectional"))
    )
    (net (code "16") (name "/GPS_ANT") (class "Default")
      (node (ref "A1") (pin "1") (pinfunction "ANT_1") (pintype "bidirectional"))
      (node (ref "U3") (pin "27") (pinfunction "RF_IN_27") (pintype "bidirectional"))
    )
    (net (code "17") (name "/GPS_VDD_SWITCHED") (class "Default")
      (node (ref "C28") (pin "1") (pinfunction "P$1_1") (pintype "passive"))
      (node (ref "C7") (pin "1") (pinfunction "P$1_1") (pintype "passive"))
      (node (ref "C9") (pin "1") (pinfunction "P$1_1") (pintype "passive"))
      (node (ref "Q1") (pin "3") (pinfunction "D_3") (pintype "passive"))
      (node (ref "U11") (pin "3") (pinfunction "VCC_3") (pintype "power_in"))
      (node (ref "U3") (pin "8") (pinfunction "VKA_8") (pintype "bidirectional"))
      (node (ref "U3") (pin "9") (pinfunction "VDD_9") (pintype "bidirectional"))
    )
    (net (code "18") (name "/HBO") (class "Default")
      (node (ref "R28") (pin "2") (pinfunction "2_2") (pintype "passive"))
      (node (ref "U12") (pin "4") (pinfunction "HBO_4") (pintype "output"))
    )
    (net (code "19") (name "/LED1") (class "Default")
      (node (ref "LED1") (pin "C") (pinfunction "C_C") (pintype "passive"))
      (node (ref "U1") (pin "16") (pinfunction "PA15_16") (pintype "bidirectional"))
    )
    (net (code "20") (name "/LF_CLOCK") (class "Default")
      (node (ref "R7") (pin "1") (pinfunction "1_1") (pintype "passive"))
      (node (ref "U1") (pin "1") (pinfunction "PA00_1") (pintype "bidirectional"))
    )
    (net (code "21") (name "/LF_CLOCK_OUT") (class "Default")
      (node (ref "R7") (pin "2") (pinfunction "2_2") (pintype "passive"))
      (node (ref "U10") (pin "2") (pinfunction "OUT_2") (pintype "output"))
    )
    (net (code "22") (name "/LIION_CAP") (class "Default")
      (node (ref "C49") (pin "1") (pinfunction "P$1_1") (pintype "passive"))
      (node (ref "D4") (pin "CATHODE") (pinfunction "C_CATHODE") (pintype "passive"))
      (node (ref "D5") (pin "ANODE") (pinfunction "A_ANODE") (pintype "passive"))
    )
    (net (code "23") (name "/MEM_CSN") (class "Default")
      (node (ref "U1") (pin "13") (pinfunction "PA10_13") (pintype "bidirectional"))
      (node (ref "U4") (pin "1") (pinfunction "~{CE}_1") (pintype "input"))
    )
    (net (code "24") (name "/MEM_MISO") (class "Default")
      (node (ref "U1") (pin "14") (pinfunction "PA11_14") (pintype "bidirectional"))
      (node (ref "U4") (pin "2") (pinfunction "SO/SIO1_2") (pintype "output"))
    )
    (net (code "25") (name "/MEM_MOSI") (class "Default")
      (node (ref "U1") (pin "11") (pinfunction "PA08_11") (pintype "bidirectional"))
      (node (ref "U4") (pin "5") (pinfunction "SI/SIO0_5") (pintype "bidirectional"))
    )
    (net (code "26") (name "/MEM_SCK") (class "Default")
      (node (ref "U1") (pin "12") (pinfunction "PA09_12") (pintype "bidirectional"))
      (node (ref "U4") (pin "6") (pinfunction "SCK_6") (pintype "input"))
    )
    (net (code "27") (name "/MEM_WPN") (class "Default")
      (node (ref "U4") (pin "3") (pinfunction "~{WP}_3") (pintype "output"))
    )
    (net (code "28") (name "/NTCBIAS") (class "Default")
      (node (ref "U12") (pin "1") (pinfunction "NTCBIAS_1") (pintype "power_in"))
    )
    (net (code "29") (name "/RADIO_VDD") (class "Default")
      (node (ref "C20") (pin "1") (pinfunction "P$1_1") (pintype "passive"))
      (node (ref "C25") (pin "1") (pinfunction "P$1_1") (pintype "passive"))
      (node (ref "C34") (pin "1") (pinfunction "P$1_1") (pintype "passive"))
      (node (ref "C8") (pin "1") (pinfunction "P$1_1") (pintype "passive"))
      (node (ref "FB1") (pin "1") (pinfunction "P$1_1") (pintype "passive"))
      (node (ref "LC") (pin "2") (pinfunction "2_2") (pintype "passive"))
      (node (ref "U16") (pin "5") (pinfunction "VCC_5") (pintype "power_in"))
      (node (ref "U2") (pin "6") (pinfunction "VDD_6") (pintype "power_in"))
      (node (ref "U2") (pin "8") (pinfunction "VDD2_8") (pintype "power_in"))
    )
    (net (code "30") (name "/RADIO_XIN") (class "Default")
      (node (ref "C13") (pin "2") (pinfunction "P$2_2") (pintype "passive"))
      (node (ref "U2") (pin "17") (pinfunction "XIN_17") (pintype "input"))
    )
    (net (code "31") (name "/RF_SW_V2") (class "Default")
      (node (ref "C47") (pin "2") (pinfunction "P$2_2") (pintype "passive"))
      (node (ref "U16") (pin "4") (pinfunction "Y_4") (pintype "output"))
      (node (ref "U19") (pin "6") (pinfunction "V2_6") (pintype "bidirectional"))
    )
    (net (code "32") (name "/RF_TCXO_REG_EN") (class "Default")
      (node (ref "U1") (pin "17") (pinfunction "PA16_17") (pintype "bidirectional"))
      (node (ref "U6") (pin "3") (pinfunction "EN_3") (pintype "input"))
    )
    (net (code "33") (name "/RTC_XI") (class "Default")
      (node (ref "R8") (pin "1") (pinfunction "1_1") (pintype "passive"))
      (node (ref "U3") (pin "12") (pinfunction "RTC_XI_12") (pintype "bidirectional"))
    )
    (net (code "34") (name "/RTC_XO") (class "Default")
      (node (ref "U3") (pin "13") (pinfunction "RTC_XO_13") (pintype "bidirectional"))
    )
    (net (code "35") (name "/RX") (class "Default")
      (node (ref "C50") (pin "1") (pinfunction "P$1_1") (pintype "passive"))
      (node (ref "C6") (pin "1") (pinfunction "P$1_1") (pintype "passive"))
      (node (ref "L7") (pin "1") (pinfunction "1_1") (pintype "passive"))
    )
    (net (code "36") (name "/SAM_XOSC") (class "Default")
      (node (ref "C18") (pin "1") (pinfunction "P$1_1") (pintype "passive"))
      (node (ref "R12") (pin "1") (pinfunction "1_1") (pintype "passive"))
      (node (ref "R13") (pin "2") (pinfunction "2_2") (pintype "passive"))
      (node (ref "U1") (pin "15") (pinfunction "PA14_15") (pintype "bidirectional"))
    )
    (net (code "37") (name "/SE_ON_OFF") (class "Default")
      (node (ref "U1") (pin "6") (pinfunction "PA05_6") (pintype "bidirectional"))
      (node (ref "U3") (pin "3") (pinfunction "ON_OFF_3") (pintype "bidirectional"))
    )
    (net (code "38") (name "/SE_TCXO_CLK") (class "Default")
      (node (ref "C14") (pin "1") (pinfunction "P$1_1") (pintype "passive"))
      (node (ref "U3") (pin "21") (pinfunction "TCXO_CLK_21") (pintype "bidirectional"))
    )
    (net (code "39") (name "/SI_GPIO0") (class "Default")
      (node (ref "C46") (pin "2") (pinfunction "P$2_2") (pintype "passive"))
      (node (ref "R22") (pin "2") (pinfunction "2_2") (pintype "passive"))
      (node (ref "R29") (pin "1") (pinfunction "1_1") (pintype "passive"))
      (node (ref "U16") (pin "2") (pinfunction "A_2") (pintype "input"))
      (node (ref "U19") (pin "4") (pinfunction "V1_4") (pintype "bidirectional"))
      (node (ref "U2") (pin "9") (pinfunction "GPIO0_9") (pintype "bidirectional"))
    )
    (net (code "40") (name "/SI_GPIO1") (class "Default")
      (node (ref "U1") (pin "24") (pinfunction "PA25_24") (pintype "bidirectional"))
      (node (ref "U2") (pin "10") (pinfunction "GPIO1_10") (pintype "bidirectional"))
    )
    (net (code "41") (name "/SI_GPIO2") (class "Default")
      (node (ref "R31") (pin "1") (pinfunction "1_1") (pintype "passive"))
      (node (ref "U17") (pin "2") (pinfunction "A_2") (pintype "input"))
      (node (ref "U2") (pin "19") (pinfunction "GPIO2_19") (pintype "bidirectional"))
    )
    (net (code "42") (name "/SI_GPIO3") (class "Default")
      (node (ref "R32") (pin "1") (pinfunction "1_1") (pintype "passive"))
      (node (ref "U18") (pin "2") (pinfunction "A_2") (pintype "input"))
      (node (ref "U2") (pin "20") (pinfunction "GPIO3_20") (pintype "bidirectional"))
    )
    (net (code "43") (name "/SI_MISO") (class "Default")
      (node (ref "U1") (pin "21") (pinfunction "PA22_21") (pintype "bidirectional"))
      (node (ref "U2") (pin "13") (pinfunction "SDO_13") (pintype "output"))
    )
    (net (code "44") (name "/SI_MOSI") (class "Default")
      (node (ref "U1") (pin "20") (pinfunction "PA19_20") (pintype "bidirectional"))
      (node (ref "U2") (pin "14") (pinfunction "SDI_14") (pintype "bidirectional"))
    )
    (net (code "45") (name "/SI_NIRQ") (class "Default")
      (node (ref "U1") (pin "23") (pinfunction "PA24_23") (pintype "bidirectional"))
      (node (ref "U2") (pin "11") (pinfunction "NIRQ_11") (pintype "output"))
    )
    (net (code "46") (name "/SI_NSEL") (class "Default")
      (node (ref "U1") (pin "19") (pinfunction "PA18_19") (pintype "bidirectional"))
      (node (ref "U2") (pin "15") (pinfunction "NSEL_15") (pintype "input"))
    )
    (net (code "47") (name "/SI_SCLK") (class "Default")
      (node (ref "U1") (pin "22") (pinfunction "PA23_22") (pintype "bidirectional"))
      (node (ref "U2") (pin "12") (pinfunction "SCLK_12") (pintype "input"))
    )
    (net (code "48") (name "/SI_SDN") (class "Default")
      (node (ref "U1") (pin "18") (pinfunction "PA17_18") (pintype "bidirectional"))
      (node (ref "U2") (pin "1") (pinfunction "SDN_1") (pintype "input"))
    )
    (net (code "49") (name "/SKY_OUT") (class "Default")
      (node (ref "C40") (pin "1") (pinfunction "P$1_1") (pintype "passive"))
      (node (ref "U20") (pin "11") (pinfunction "RFC_11") (pintype "bidirectional"))
    )
    (net (code "50") (name "/SKY_V1") (class "Default")
      (node (ref "R20") (pin "1") (pinfunction "1_1") (pintype "passive"))
      (node (ref "U20") (pin "4") (pinfunction "V1_4") (pintype "bidirectional"))
    )
    (net (code "51") (name "/SKY_V1_1") (class "Default")
      (node (ref "R20") (pin "2") (pinfunction "2_2") (pintype "passive"))
      (node (ref "U17") (pin "4") (pinfunction "Y_4") (pintype "output"))
    )
    (net (code "52") (name "/SKY_V2") (class "Default")
      (node (ref "R21") (pin "1") (pinfunction "1_1") (pintype "passive"))
      (node (ref "U20") (pin "5") (pinfunction "V2_5") (pintype "bidirectional"))
    )
    (net (code "53") (name "/SKY_V2_1") (class "Default")
      (node (ref "R21") (pin "2") (pinfunction "2_2") (pintype "passive"))
      (node (ref "U18") (pin "4") (pinfunction "Y_4") (pintype "output"))
    )
    (net (code "54") (name "/SOLAR1") (class "Default")
      (node (ref "D1") (pin "ANODE") (pinfunction "A_ANODE") (pintype "passive"))
    )
    (net (code "55") (name "/SOLAR2") (class "Default")
      (node (ref "D2") (pin "ANODE") (pinfunction "A_ANODE") (pintype "passive"))
    )
    (net (code "56") (name "/SWDCLK") (class "Default")
      (node (ref "JTAG1") (pin "4") (pinfunction "4_4") (pintype "passive"))
      (node (ref "U1") (pin "31") (pinfunction "PA30/SWCLK_31") (pintype "bidirectional"))
    )
    (net (code "57") (name "/SWDIO") (class "Default")
      (node (ref "JTAG1") (pin "2") (pinfunction "2_2") (pintype "passive"))
      (node (ref "U1") (pin "32") (pinfunction "PA31/SWDIO_32") (pintype "bidirectional"))
    )
    (net (code "58") (name "/TCXO_OUT") (class "Default")
      (node (ref "C13") (pin "1") (pinfunction "P$1_1") (pintype "passive"))
      (node (ref "C14") (pin "2") (pinfunction "P$2_2") (pintype "passive"))
      (node (ref "C18") (pin "2") (pinfunction "P$2_2") (pintype "passive"))
      (node (ref "U5") (pin "3") (pinfunction "OUT_3") (pintype "output"))
    )
    (net (code "59") (name "/TCXO_REG_IN") (class "Default")
      (node (ref "C23") (pin "1") (pinfunction "P$1_1") (pintype "passive"))
      (node (ref "FB2") (pin "1") (pinfunction "P$1_1") (pintype "passive"))
      (node (ref "U6") (pin "1") (pinfunction "IN_1") (pintype "power_in"))
    )
    (net (code "60") (name "/TCXO_VDD") (class "Default")
      (node (ref "C24") (pin "1") (pinfunction "P$1_1") (pintype "passive"))
      (node (ref "U5") (pin "4") (pinfunction "VCC_4") (pintype "power_in"))
      (node (ref "U6") (pin "5") (pinfunction "OUT_5") (pintype "output"))
    )
    (net (code "61") (name "/TIMEPULSE") (class "Default")
      (node (ref "U3") (pin "4") (pinfunction "TM_4") (pintype "bidirectional"))
    )
    (net (code "62") (name "/TX") (class "Default")
      (node (ref "C1") (pin "1") (pinfunction "P$1_1") (pintype "passive"))
      (node (ref "C44") (pin "1") (pinfunction "P$1_1") (pintype "passive"))
      (node (ref "L5") (pin "1") (pinfunction "1_1") (pintype "passive"))
    )
    (net (code "63") (name "/TX_1") (class "Default")
      (node (ref "C44") (pin "2") (pinfunction "P$2_2") (pintype "passive"))
      (node (ref "U19") (pin "5") (pinfunction "J1_5") (pintype "bidirectional"))
    )
    (net (code "64") (name "/V_BUS") (class "Default")
      (node (ref "C11") (pin "1") (pinfunction "P$1_1") (pintype "passive"))
      (node (ref "C52") (pin "1") (pinfunction "P$1_1") (pintype "passive"))
      (node (ref "D1") (pin "CATHODE") (pinfunction "C_CATHODE") (pintype "passive"))
      (node (ref "D2") (pin "CATHODE") (pinfunction "C_CATHODE") (pintype "passive"))
      (node (ref "D3") (pin "CATHODE") (pinfunction "C_CATHODE") (pintype "passive"))
      (node (ref "D5") (pin "CATHODE") (pinfunction "C_CATHODE") (pintype "passive"))
      (node (ref "DZ1") (pin "C") (pinfunction "C_C") (pintype "passive"))
      (node (ref "JP2") (pin "1") (pinfunction "1_1") (pintype "passive"))
      (node (ref "Q2") (pin "2") (pinfunction "S_2") (pintype "passive"))
      (node (ref "Q3") (pin "2") (pinfunction "S_2") (pintype "passive"))
      (node (ref "R10") (pin "1") (pinfunction "1_1") (pintype "passive"))
      (node (ref "R26") (pin "2") (pinfunction "2_2") (pintype "passive"))
      (node (ref "R30") (pin "1") (pinfunction "1_1") (pintype "passive"))
      (node (ref "R6") (pin "1") (pinfunction "1_1") (pintype "passive"))
      (node (ref "U15") (pin "4") (pinfunction "IN_4") (pintype "power_in"))
      (node (ref "U9") (pin "5") (pinfunction "VIN_5") (pintype "bidirectional"))
    )
    (net (code "65") (name "/V_BUS_SENSE") (class "Default")
      (node (ref "R26") (pin "1") (pinfunction "1_1") (pintype "passive"))
      (node (ref "R27") (pin "2") (pinfunction "2_2") (pintype "passive"))
      (node (ref "U1") (pin "4") (pinfunction "PA03_4") (pintype "bidirectional"))
    )
    (net (code "66") (name "/V_GG") (class "Default")
      (node (ref "C26") (pin "1") (pinfunction "P$1_1") (pintype "passive"))
      (node (ref "R19") (pin "2") (pinfunction "2_2") (pintype "passive"))
      (node (ref "U14") (pin "5") (pinfunction "OUT_5") (pintype "output"))
    )
    (net (code "67") (name "/V_SKY") (class "Default")
      (node (ref "C35") (pin "1") (pinfunction "P$1_1") (pintype "passive"))
      (node (ref "U15") (pin "5") (pinfunction "OUT_5") (pintype "output"))
      (node (ref "U20") (pin "6") (pinfunction "VDD_6") (pintype "bidirectional"))
    )
    (net (code "68") (name "/WDI") (class "Default")
      (node (ref "R17") (pin "2") (pinfunction "2_2") (pintype "passive"))
      (node (ref "U1") (pin "27") (pinfunction "PA28_27") (pintype "bidirectional"))
      (node (ref "U7") (pin "4") (pinfunction "WDI_4") (pintype "bidirectional"))
    )
    (net (code "69") (name "/WDI~{RESET}") (class "Default")
      (node (ref "R16") (pin "2") (pinfunction "2_2") (pintype "passive"))
      (node (ref "U7") (pin "1") (pinfunction "~{RESET}_1") (pintype "bidirectional"))
      (node (ref "U8") (pin "2") (pinfunction "B_2") (pintype "input"))
    )
    (net (code "70") (name "/~{GPS_EN}") (class "Default")
      (node (ref "Q1") (pin "1") (pinfunction "G_1") (pintype "passive"))
      (node (ref "R15") (pin "1") (pinfunction "1_1") (pintype "passive"))
      (node (ref "U1") (pin "2") (pinfunction "PA01_2") (pintype "bidirectional"))
    )
    (net (code "71") (name "/~{RESET}") (class "Default")
      (node (ref "U1") (pin "26") (pinfunction "RESETN_26") (pintype "input"))
      (node (ref "U8") (pin "4") (pinfunction "Y_4") (pintype "output"))
    )
    (net (code "72") (name "1.8V") (class "Default")
      (node (ref "C10") (pin "1") (pinfunction "P$1_1") (pintype "passive"))
      (node (ref "C15") (pin "1") (pinfunction "P$1_1") (pintype "passive"))
      (node (ref "C17") (pin "1") (pinfunction "P$1_1") (pintype "passive"))
      (node (ref "C21") (pin "1") (pinfunction "P$1_1") (pintype "passive"))
      (node (ref "C32") (pin "1") (pinfunction "1_1") (pintype "passive"))
      (node (ref "C33") (pin "1") (pinfunction "1_1") (pintype "passive"))
      (node (ref "FB1") (pin "2") (pinfunction "P$2_2") (pintype "passive"))
      (node (ref "FB2") (pin "2") (pinfunction "P$2_2") (pintype "passive"))
      (node (ref "FB3") (pin "2") (pinfunction "P$2_2") (pintype "passive"))
      (node (ref "JTAG1") (pin "1") (pinfunction "1_1") (pintype "passive"))
      (node (ref "L2") (pin "2") (pinfunction "2_2") (pintype "passive"))
      (node (ref "LED1") (pin "A") (pinfunction "A_A") (pintype "passive"))
      (node (ref "R12") (pin "2") (pinfunction "2_2") (pintype "passive"))
      (node (ref "R31") (pin "2") (pinfunction "2_2") (pintype "passive"))
      (node (ref "R32") (pin "2") (pinfunction "2_2") (pintype "passive"))
      (node (ref "R4") (pin "2") (pinfunction "2_2") (pintype "passive"))
      (node (ref "U1") (pin "30") (pinfunction "VDD_30") (pintype "power_in"))
      (node (ref "U1") (pin "9") (pinfunction "VDD_ANA_9") (pintype "power_in"))
      (node (ref "U10") (pin "3") (pinfunction "VCC_3") (pintype "power_in"))
      (node (ref "U17") (pin "5") (pinfunction "VCC_5") (pintype "power_in"))
      (node (ref "U18") (pin "5") (pinfunction "VCC_5") (pintype "power_in"))
      (node (ref "U4") (pin "7") (pinfunction "~{HOLD}_7") (pintype "output"))
      (node (ref "U4") (pin "8") (pinfunction "VDD_8") (pintype "power_in"))
      (node (ref "U7") (pin "3") (pinfunction "~{MR}_3") (pintype "bidirectional"))
      (node (ref "U7") (pin "5") (pinfunction "VDD_5") (pintype "bidirectional"))
      (node (ref "U8") (pin "5") (pinfunction "VCC_5") (pintype "power_in"))
      (node (ref "U9") (pin "3") (pinfunction "FB_3") (pintype "bidirectional"))
    )
    (net (code "73") (name "GND") (class "Default")
      (node (ref "C1") (pin "2") (pinfunction "P$2_2") (pintype "passive"))
      (node (ref "C10") (pin "2") (pinfunction "P$2_2") (pintype "passive"))
      (node (ref "C11") (pin "2") (pinfunction "P$2_2") (pintype "passive"))
      (node (ref "C12") (pin "2") (pinfunction "P$2_2") (pintype "passive"))
      (node (ref "C15") (pin "2") (pinfunction "P$2_2") (pintype "passive"))
      (node (ref "C16") (pin "2") (pinfunction "P$2_2") (pintype "passive"))
      (node (ref "C17") (pin "2") (pinfunction "P$2_2") (pintype "passive"))
      (node (ref "C19") (pin "2") (pinfunction "P$2_2") (pintype "passive"))
      (node (ref "C2") (pin "2") (pinfunction "P$2_2") (pintype "passive"))
      (node (ref "C20") (pin "2") (pinfunction "P$2_2") (pintype "passive"))
      (node (ref "C21") (pin "2") (pinfunction "P$2_2") (pintype "passive"))
      (node (ref "C22") (pin "2") (pinfunction "2_2") (pintype "passive"))
      (node (ref "C23") (pin "2") (pinfunction "P$2_2") (pintype "passive"))
      (node (ref "C24") (pin "2") (pinfunction "P$2_2") (pintype "passive"))
      (node (ref "C25") (pin "2") (pinfunction "P$2_2") (pintype "passive"))
      (node (ref "C26") (pin "2") (pinfunction "P$2_2") (pintype "passive"))
      (node (ref "C27") (pin "2") (pinfunction "2_2") (pintype "passive"))
      (node (ref "C28") (pin "2") (pinfunction "P$2_2") (pintype "passive"))
      (node (ref "C29") (pin "2") (pinfunction "2_2") (pintype "passive"))
      (node (ref "C3") (pin "2") (pinfunction "P$2_2") (pintype "passive"))
      (node (ref "C30") (pin "2") (pinfunction "P$2_2") (pintype "passive"))
      (node (ref "C31") (pin "2") (pinfunction "P$2_2") (pintype "passive"))
      (node (ref "C32") (pin "2") (pinfunction "2_2") (pintype "passive"))
      (node (ref "C33") (pin "2") (pinfunction "2_2") (pintype "passive"))
      (node (ref "C34") (pin "2") (pinfunction "P$2_2") (pintype "passive"))
      (node (ref "C35") (pin "2") (pinfunction "P$2_2") (pintype "passive"))
      (node (ref "C36") (pin "2") (pinfunction "P$2_2") (pintype "passive"))
      (node (ref "C37") (pin "2") (pinfunction "P$2_2") (pintype "passive"))
      (node (ref "C38") (pin "2") (pinfunction "P$2_2") (pintype "passive"))
      (node (ref "C4") (pin "2") (pinfunction "P$2_2") (pintype "passive"))
      (node (ref "C43") (pin "2") (pinfunction "P$2_2") (pintype "passive"))
      (node (ref "C46") (pin "1") (pinfunction "P$1_1") (pintype "passive"))
      (node (ref "C47") (pin "1") (pinfunction "P$1_1") (pintype "passive"))
      (node (ref "C48") (pin "2") (pinfunction "P$2_2") (pintype "passive"))
      (node (ref "C49") (pin "2") (pinfunction "P$2_2") (pintype "passive"))
      (node (ref "C5") (pin "2") (pinfunction "P$2_2") (pintype "passive"))
      (node (ref "C51") (pin "2") (pinfunction "P$2_2") (pintype "passive"))
      (node (ref "C52") (pin "2") (pinfunction "P$2_2") (pintype "passive"))
      (node (ref "C7") (pin "2") (pinfunction "P$2_2") (pintype "passive"))
      (node (ref "C8") (pin "2") (pinfunction "P$2_2") (pintype "passive"))
      (node (ref "C9") (pin "2") (pinfunction "P$2_2") (pintype "passive"))
      (node (ref "DZ1") (pin "A") (pinfunction "A_A") (pintype "passive"))
      (node (ref "JP1") (pin "2") (pinfunction "2_2") (pintype "passive"))
      (node (ref "JP2") (pin "2") (pinfunction "2_2") (pintype "passive"))
      (node (ref "JP3") (pin "2") (pinfunction "2_2") (pintype "passive"))
      (node (ref "JTAG1") (pin "3") (pinfunction "3_3") (pintype "passive"))
      (node (ref "JTAG1") (pin "5") (pinfunction "5_5") (pintype "passive"))
      (node (ref "LED2") (pin "C") (pinfunction "C_C") (pintype "passive"))
      (node (ref "Q5") (pin "P1") (pinfunction "E_P1") (pintype "passive"))
      (node (ref "Q5") (pin "P4") (pinfunction "E_P4") (pintype "passive"))
      (node (ref "Q6") (pin "2") (pinfunction "S_2") (pintype "bidirectional"))
      (node (ref "Q6") (pin "2.1") (pinfunction "S_2.1") (pintype "bidirectional"))
      (node (ref "R1") (pin "1") (pinfunction "1_1") (pintype "passive"))
      (node (ref "R11") (pin "1") (pinfunction "1_1") (pintype "passive"))
      (node (ref "R13") (pin "1") (pinfunction "1_1") (pintype "passive"))
      (node (ref "R14") (pin "1") (pinfunction "1_1") (pintype "passive"))
      (node (ref "R16") (pin "1") (pinfunction "1_1") (pintype "passive"))
      (node (ref "R17") (pin "1") (pinfunction "1_1") (pintype "passive"))
      (node (ref "R2") (pin "1") (pinfunction "1_1") (pintype "passive"))
      (node (ref "R22") (pin "1") (pinfunction "1_1") (pintype "passive"))
      (node (ref "R24") (pin "1") (pinfunction "1_1") (pintype "passive"))
      (node (ref "R27") (pin "1") (pinfunction "1_1") (pintype "passive"))
      (node (ref "R3") (pin "1") (pinfunction "1_1") (pintype "passive"))
      (node (ref "R5") (pin "1") (pinfunction "1_1") (pintype "passive"))
      (node (ref "U1") (pin "10") (pinfunction "GND1_10") (pintype "power_in"))
      (node (ref "U1") (pin "28") (pinfunction "GND2_28") (pintype "power_in"))
      (node (ref "U1") (pin "33") (pinfunction "GND_33") (pintype "power_in"))
      (node (ref "U10") (pin "1") (pinfunction "GND_1") (pintype "power_in"))
      (node (ref "U10") (pin "4") (pinfunction "GND1_4") (pintype "power_in"))
      (node (ref "U11") (pin "1") (pinfunction "GND_1") (pintype "power_in"))
      (node (ref "U11") (pin "4") (pinfunction "GND1_4") (pintype "power_in"))
      (node (ref "U12") (pin "3") (pinfunction "ADJ_3") (pintype "input"))
      (node (ref "U12") (pin "5") (pinfunction "GND_5") (pintype "passive"))
      (node (ref "U12") (pin "9") (pinfunction "EP_9") (pintype "passive"))
      (node (ref "U13") (pin "11") (pinfunction "EP_11") (pintype "passive"))
      (node (ref "U13") (pin "4") (pinfunction "GND_2_4") (pintype "passive"))
      (node (ref "U13") (pin "5") (pinfunction "GND_5") (pintype "passive"))
      (node (ref "U14") (pin "2") (pinfunction "GND_2") (pintype "passive"))
      (node (ref "U15") (pin "2") (pinfunction "GND_2") (pintype "passive"))
      (node (ref "U16") (pin "3") (pinfunction "GND_3") (pintype "passive"))
      (node (ref "U17") (pin "3") (pinfunction "GND_3") (pintype "passive"))
      (node (ref "U18") (pin "3") (pinfunction "GND_3") (pintype "passive"))
      (node (ref "U19") (pin "2") (pinfunction "GND_2") (pintype "bidirectional"))
      (node (ref "U2") (pin "18") (pinfunction "GND2_18") (pintype "power_in"))
      (node (ref "U2") (pin "5") (pinfunction "NC/GND_5") (pintype "bidirectional"))
      (node (ref "U2") (pin "PAD") (pinfunction "GND_PAD") (pintype "power_in"))
      (node (ref "U20") (pin "10") (pinfunction "GND3_10") (pintype "bidirectional"))
      (node (ref "U20") (pin "12") (pinfunction "GND4_12") (pintype "bidirectional"))
      (node (ref "U20") (pin "2") (pinfunction "GND_2") (pintype "bidirectional"))
      (node (ref "U20") (pin "7") (pinfunction "GND1_7") (pintype "bidirectional"))
      (node (ref "U20") (pin "8") (pinfunction "GND2_8") (pintype "bidirectional"))
      (node (ref "U20") (pin "PAD") (pinfunction "PAD_PAD") (pintype "bidirectional"))
      (node (ref "U3") (pin "1") (pinfunction "GND1_1") (pintype "bidirectional"))
      (node (ref "U3") (pin "18") (pinfunction "GND3_18") (pintype "bidirectional"))
      (node (ref "U3") (pin "20") (pinfunction "GND4_20") (pintype "bidirectional"))
      (node (ref "U3") (pin "23") (pinfunction "GND5_23") (pintype "bidirectional"))
      (node (ref "U3") (pin "24") (pinfunction "GND6_24") (pintype "bidirectional"))
      (node (ref "U3") (pin "25") (pinfunction "GND7_25") (pintype "bidirectional"))
      (node (ref "U3") (pin "26") (pinfunction "GND8_26") (pintype "bidirectional"))
      (node (ref "U3") (pin "28") (pinfunction "GND9_28") (pintype "bidirectional"))
      (node (ref "U3") (pin "29") (pinfunction "GND10_29") (pintype "bidirectional"))
      (node (ref "U3") (pin "5") (pinfunction "GND2_5") (pintype "bidirectional"))
      (node (ref "U4") (pin "4") (pinfunction "VSS_4") (pintype "power_in"))
      (node (ref "U5") (pin "2") (pinfunction "GND_2") (pintype "power_in"))
      (node (ref "U6") (pin "2") (pinfunction "GND_2") (pintype "passive"))
      (node (ref "U7") (pin "2") (pinfunction "GND_2") (pintype "bidirectional"))
      (node (ref "U8") (pin "3") (pinfunction "GND_3") (pintype "passive"))
      (node (ref "U9") (pin "2") (pinfunction "MODE_2") (pintype "bidirectional"))
      (node (ref "U9") (pin "6") (pinfunction "GND_6") (pintype "bidirectional"))
      (node (ref "U9") (pin "PAD") (pinfunction "GND2_PAD") (pintype "bidirectional"))
    )
    (net (code "74") (name "Net-(C0-P$1)") (class "Default")
      (node (ref "C0") (pin "1") (pinfunction "P$1_1") (pintype "passive"))
      (node (ref "L0") (pin "2") (pinfunction "2_2") (pintype "passive"))
    )
    (net (code "75") (name "Net-(C0-P$2)") (class "Default")
      (node (ref "C0") (pin "2") (pinfunction "P$2_2") (pintype "passive"))
      (node (ref "LC") (pin "1") (pinfunction "1_1") (pintype "passive"))
      (node (ref "U2") (pin "4") (pinfunction "TX_4") (pintype "output"))
    )
    (net (code "76") (name "Net-(C2-P$1)") (class "Default")
      (node (ref "C2") (pin "1") (pinfunction "P$1_1") (pintype "passive"))
      (node (ref "L4") (pin "1") (pinfunction "1_1") (pintype "passive"))
      (node (ref "L5") (pin "2") (pinfunction "2_2") (pintype "passive"))
    )
    (net (code "77") (name "Net-(C3-P$1)") (class "Default")
      (node (ref "C3") (pin "1") (pinfunction "P$1_1") (pintype "passive"))
      (node (ref "L0") (pin "1") (pinfunction "1_1") (pintype "passive"))
      (node (ref "L4") (pin "2") (pinfunction "2_2") (pintype "passive"))
    )
    (net (code "78") (name "Net-(C4-P$1)") (class "Default")
      (node (ref "C4") (pin "1") (pinfunction "P$1_1") (pintype "passive"))
      (node (ref "C40") (pin "2") (pinfunction "P$2_2") (pintype "passive"))
      (node (ref "L12") (pin "1") (pinfunction "1_1") (pintype "passive"))
    )
    (net (code "79") (name "Net-(C5-P$1)") (class "Default")
      (node (ref "C5") (pin "1") (pinfunction "P$1_1") (pintype "passive"))
      (node (ref "L6") (pin "1") (pinfunction "1_1") (pintype "passive"))
      (node (ref "L7") (pin "2") (pinfunction "2_2") (pintype "passive"))
      (node (ref "U2") (pin "2") (pinfunction "RXP_2") (pintype "input"))
    )
    (net (code "80") (name "Net-(C6-P$2)") (class "Default")
      (node (ref "C6") (pin "2") (pinfunction "P$2_2") (pintype "passive"))
      (node (ref "L6") (pin "2") (pinfunction "2_2") (pintype "passive"))
      (node (ref "U2") (pin "3") (pinfunction "RXN_3") (pintype "input"))
    )
    (net (code "81") (name "Net-(C12-P$1)") (class "Default")
      (node (ref "C12") (pin "1") (pinfunction "P$1_1") (pintype "passive"))
      (node (ref "U6") (pin "4") (pinfunction "NR/FB_4") (pintype "passive"))
    )
    (net (code "82") (name "Net-(C16-P$1)") (class "Default")
      (node (ref "C16") (pin "1") (pinfunction "P$1_1") (pintype "passive"))
      (node (ref "U1") (pin "29") (pinfunction "VDD_CORE_29") (pintype "power_in"))
    )
    (net (code "83") (name "Net-(C19-P$1)") (class "Default")
      (node (ref "C19") (pin "1") (pinfunction "P$1_1") (pintype "passive"))
      (node (ref "R18") (pin "1") (pinfunction "1_1") (pintype "passive"))
    )
    (net (code "84") (name "Net-(C31-P$1)") (class "Default")
      (node (ref "C31") (pin "1") (pinfunction "P$1_1") (pintype "passive"))
      (node (ref "U13") (pin "10") (pinfunction "SS_10") (pintype "input"))
    )
    (net (code "85") (name "Net-(C36-P$1)") (class "Default")
      (node (ref "C36") (pin "1") (pinfunction "P$1_1") (pintype "passive"))
      (node (ref "C39") (pin "2") (pinfunction "P$2_2") (pintype "passive"))
      (node (ref "L9") (pin "1") (pinfunction "1_1") (pintype "passive"))
    )
    (net (code "86") (name "Net-(C37-P$1)") (class "Default")
      (node (ref "C37") (pin "1") (pinfunction "P$1_1") (pintype "passive"))
      (node (ref "L10") (pin "1") (pinfunction "1_1") (pintype "passive"))
      (node (ref "L9") (pin "2") (pinfunction "2_2") (pintype "passive"))
    )
    (net (code "87") (name "Net-(C39-P$1)") (class "Default")
      (node (ref "C39") (pin "1") (pinfunction "P$1_1") (pintype "passive"))
      (node (ref "L3") (pin "1") (pinfunction "1_1") (pintype "passive"))
      (node (ref "Q6") (pin "3") (pinfunction "D_3") (pintype "bidirectional"))
    )
    (net (code "88") (name "Net-(C41-P$1)") (class "Default")
      (node (ref "C41") (pin "1") (pinfunction "P$1_1") (pintype "passive"))
      (node (ref "U19") (pin "3") (pinfunction "J2_3") (pintype "bidirectional"))
    )
    (net (code "89") (name "Net-(C41-P$2)") (class "Default")
      (node (ref "C41") (pin "2") (pinfunction "P$2_2") (pintype "passive"))
      (node (ref "C43") (pin "1") (pinfunction "P$1_1") (pintype "passive"))
      (node (ref "L11") (pin "1") (pinfunction "1_1") (pintype "passive"))
    )
    (net (code "90") (name "Net-(C42-P$1)") (class "Default")
      (node (ref "C42") (pin "1") (pinfunction "P$1_1") (pintype "passive"))
      (node (ref "U19") (pin "1") (pinfunction "J3_1") (pintype "bidirectional"))
    )
    (net (code "91") (name "Net-(C45-P$2)") (class "Default")
      (node (ref "C45") (pin "2") (pinfunction "P$2_2") (pintype "passive"))
      (node (ref "U20") (pin "1") (pinfunction "J1_1") (pintype "bidirectional"))
    )
    (net (code "92") (name "Net-(C50-P$2)") (class "Default")
      (node (ref "C50") (pin "2") (pinfunction "P$2_2") (pintype "passive"))
      (node (ref "U20") (pin "9") (pinfunction "J2_9") (pintype "bidirectional"))
    )
    (net (code "93") (name "Net-(D4-A)") (class "Default")
      (node (ref "D4") (pin "ANODE") (pinfunction "A_ANODE") (pintype "passive"))
      (node (ref "R23") (pin "1") (pinfunction "1_1") (pintype "passive"))
    )
    (net (code "94") (name "Net-(FB3-P$1)") (class "Default")
      (node (ref "FB3") (pin "1") (pinfunction "P$1_1") (pintype "passive"))
      (node (ref "Q1") (pin "2") (pinfunction "S_2") (pintype "passive"))
      (node (ref "R15") (pin "2") (pinfunction "2_2") (pintype "passive"))
    )
    (net (code "95") (name "Net-(LED2-PadA)") (class "Default")
      (node (ref "LED2") (pin "A") (pinfunction "A_A") (pintype "passive"))
      (node (ref "R28") (pin "1") (pinfunction "1_1") (pintype "passive"))
    )
    (net (code "96") (name "Net-(Q2-G)") (class "Default")
      (node (ref "Q2") (pin "1") (pinfunction "G_1") (pintype "passive"))
      (node (ref "Q5") (pin "P3") (pinfunction "C_P3") (pintype "passive"))
      (node (ref "Q5") (pin "P8") (pinfunction "C_P8") (pintype "passive"))
      (node (ref "R10") (pin "2") (pinfunction "2_2") (pintype "passive"))
    )
    (net (code "97") (name "Net-(Q3-D)") (class "Default")
      (node (ref "Q3") (pin "3") (pinfunction "D_3") (pintype "passive"))
      (node (ref "Q4") (pin "2") (pinfunction "S_2") (pintype "passive"))
    )
    (net (code "98") (name "Net-(Q3-G)") (class "Default")
      (node (ref "Q3") (pin "1") (pinfunction "G_1") (pintype "passive"))
      (node (ref "Q4") (pin "1") (pinfunction "G_1") (pintype "passive"))
      (node (ref "Q5") (pin "P6") (pinfunction "C_P6") (pintype "passive"))
      (node (ref "Q5") (pin "P7") (pinfunction "C_P7") (pintype "passive"))
      (node (ref "R6") (pin "2") (pinfunction "2_2") (pintype "passive"))
    )
    (net (code "99") (name "Net-(Q5A-B)") (class "Default")
      (node (ref "Q5") (pin "P2") (pinfunction "B_P2") (pintype "passive"))
      (node (ref "R29") (pin "2") (pinfunction "2_2") (pintype "passive"))
    )
    (net (code "100") (name "Net-(Q5B-B)") (class "Default")
      (node (ref "Q5") (pin "P5") (pinfunction "B_P5") (pintype "passive"))
      (node (ref "R33") (pin "2") (pinfunction "2_2") (pintype "passive"))
    )
    (net (code "101") (name "Net-(Q6-G)") (class "Default")
      (node (ref "L11") (pin "2") (pinfunction "2_2") (pintype "passive"))
      (node (ref "Q6") (pin "1") (pinfunction "G_1") (pintype "bidirectional"))
      (node (ref "R19") (pin "1") (pinfunction "1_1") (pintype "passive"))
    )
    (net (code "102") (name "Net-(U3-CTS_SPI)") (class "Default")
      (node (ref "R4") (pin "1") (pinfunction "1_1") (pintype "passive"))
      (node (ref "U3") (pin "31") (pinfunction "CTS_SPI_31") (pintype "bidirectional"))
    )
    (net (code "103") (name "Net-(U3-GPIO0)") (class "Default")
      (node (ref "R2") (pin "2") (pinfunction "2_2") (pintype "passive"))
      (node (ref "U3") (pin "17") (pinfunction "GPIO0_17") (pintype "bidirectional"))
    )
    (net (code "104") (name "Net-(U3-GPIO1)") (class "Default")
      (node (ref "R3") (pin "2") (pinfunction "2_2") (pintype "passive"))
      (node (ref "U3") (pin "16") (pinfunction "GPIO1_16") (pintype "bidirectional"))
    )
    (net (code "105") (name "Net-(U3-VBB_I)") (class "Default")
      (node (ref "L8") (pin "1") (pinfunction "1_1") (pintype "passive"))
      (node (ref "U3") (pin "6") (pinfunction "VBB_I_6") (pintype "bidirectional"))
    )
    (net (code "106") (name "Net-(U3-VREG_O)") (class "Default")
      (node (ref "L8") (pin "2") (pinfunction "2_2") (pintype "passive"))
      (node (ref "U3") (pin "7") (pinfunction "VREG_O_7") (pintype "bidirectional"))
    )
    (net (code "107") (name "Net-(U9-SW)") (class "Default")
      (node (ref "L2") (pin "1") (pinfunction "1_1") (pintype "passive"))
      (node (ref "U9") (pin "1") (pinfunction "SW_1") (pintype "bidirectional"))
    )
    (net (code "108") (name "Net-(U11-OUT)") (class "Default")
      (node (ref "R8") (pin "2") (pinfunction "2_2") (pintype "passive"))
      (node (ref "U11") (pin "2") (pinfunction "OUT_2") (pintype "output"))
    )
    (net (code "109") (name "Net-(U13-CLRES)") (class "Default")
      (node (ref "R14") (pin "2") (pinfunction "2_2") (pintype "passive"))
      (node (ref "U13") (pin "9") (pinfunction "CLRES_9") (pintype "input"))
    )
    (net (code "110") (name "Net-(U13-COMP)") (class "Default")
      (node (ref "R18") (pin "2") (pinfunction "2_2") (pintype "passive"))
      (node (ref "U13") (pin "1") (pinfunction "COMP_1") (pintype "input"))
    )
    (net (code "111") (name "unconnected-(A1-N{slash}C-Pad2)") (class "Default")
      (node (ref "A1") (pin "2") (pinfunction "N/C_2") (pintype "input"))
    )
    (net (code "112") (name "unconnected-(JTAG1-Pad6)") (class "Default")
      (node (ref "JTAG1") (pin "6") (pinfunction "6_6") (pintype "passive"))
    )
    (net (code "113") (name "unconnected-(JTAG1-Pad7)") (class "Default")
      (node (ref "JTAG1") (pin "7") (pinfunction "7_7") (pintype "passive"))
    )
    (net (code "114") (name "unconnected-(JTAG1-Pad8)") (class "Default")
      (node (ref "JTAG1") (pin "8") (pinfunction "8_8") (pintype "passive"))
    )
    (net (code "115") (name "unconnected-(JTAG1-Pad9)") (class "Default")
      (node (ref "JTAG1") (pin "9") (pinfunction "9_9") (pintype "passive"))
    )
    (net (code "116") (name "unconnected-(U2-TXRAMP-Pad7)") (class "Default")
      (node (ref "U2") (pin "7") (pinfunction "TXRAMP_7") (pintype "bidirectional"))
    )
    (net (code "117") (name "unconnected-(U2-XOUT-Pad16)") (class "Default")
      (node (ref "U2") (pin "16") (pinfunction "XOUT_16") (pintype "output"))
    )
    (net (code "118") (name "unconnected-(U3-GPIO2-Pad15)") (class "Default")
      (node (ref "U3") (pin "15") (pinfunction "GPIO2_15") (pintype "bidirectional"))
    )
    (net (code "119") (name "unconnected-(U3-GPIO3-Pad11)") (class "Default")
      (node (ref "U3") (pin "11") (pinfunction "GPIO3_11") (pintype "bidirectional"))
    )
    (net (code "120") (name "unconnected-(U3-GPIO4-Pad14)") (class "Default")
      (node (ref "U3") (pin "14") (pinfunction "GPIO4_14") (pintype "bidirectional"))
    )
    (net (code "121") (name "unconnected-(U3-GPIO8-Pad10)") (class "Default")
      (node (ref "U3") (pin "10") (pinfunction "GPIO8_10") (pintype "bidirectional"))
    )
    (net (code "122") (name "unconnected-(U3-NSRESET-Pad30)") (class "Default")
      (node (ref "U3") (pin "30") (pinfunction "NSRESET_30") (pintype "bidirectional"))
    )
    (net (code "123") (name "unconnected-(U3-RTS_SPI-Pad32)") (class "Default")
      (node (ref "U3") (pin "32") (pinfunction "RTS_SPI_32") (pintype "bidirectional"))
    )
    (net (code "124") (name "unconnected-(U3-SYSTEM_ON-Pad2)") (class "Default")
      (node (ref "U3") (pin "2") (pinfunction "SYSTEM_ON_2") (pintype "bidirectional"))
    )
    (net (code "125") (name "unconnected-(U3-VCC_TCXO-Pad19)") (class "Default")
      (node (ref "U3") (pin "19") (pinfunction "VCC_TCXO_19") (pintype "bidirectional"))
    )
    (net (code "126") (name "unconnected-(U3-XTAL_CLK-Pad22)") (class "Default")
      (node (ref "U3") (pin "22") (pinfunction "XTAL_CLK_22") (pintype "bidirectional"))
    )
    (net (code "127") (name "unconnected-(U5-NC-Pad1)") (class "Default")
      (node (ref "U5") (pin "1") (pinfunction "NC_1") (pintype "no_connect"))
    )
    (net (code "128") (name "unconnected-(U12-DRV-Pad7)") (class "Default")
      (node (ref "U12") (pin "7") (pinfunction "DRV_7") (pintype "output"))
    )
    (net (code "129") (name "unconnected-(U12-LBO-Pad6)") (class "Default")
      (node (ref "U12") (pin "6") (pinfunction "LBO_6") (pintype "output"))
    )
    (net (code "130") (name "unconnected-(U14-NC-Pad3)") (class "Default")
      (node (ref "U14") (pin "3") (pinfunction "NC_3") (pintype "no_connect"))
    )
    (net (code "131") (name "unconnected-(U14-NC_2-Pad1)") (class "Default")
      (node (ref "U14") (pin "1") (pinfunction "NC_2_1") (pintype "no_connect"))
    )
    (net (code "132") (name "unconnected-(U15-NC-Pad3)") (class "Default")
      (node (ref "U15") (pin "3") (pinfunction "NC_3") (pintype "no_connect"))
    )
    (net (code "133") (name "unconnected-(U15-NC_2-Pad1)") (class "Default")
      (node (ref "U15") (pin "1") (pinfunction "NC_2_1") (pintype "no_connect"))
    )
    (net (code "134") (name "unconnected-(U16-N.C.-Pad1)") (class "Default")
      (node (ref "U16") (pin "1") (pinfunction "N.C._1") (pintype "no_connect"))
    )
    (net (code "135") (name "unconnected-(U17-N.C.-Pad1)") (class "Default")
      (node (ref "U17") (pin "1") (pinfunction "N.C._1") (pintype "no_connect"))
    )
    (net (code "136") (name "unconnected-(U18-N.C.-Pad1)") (class "Default")
      (node (ref "U18") (pin "1") (pinfunction "N.C._1") (pintype "no_connect"))
    )
  )
)
